# GS_02_Pow.net
KiCad netlist of a schematic drawn in Altium Designer
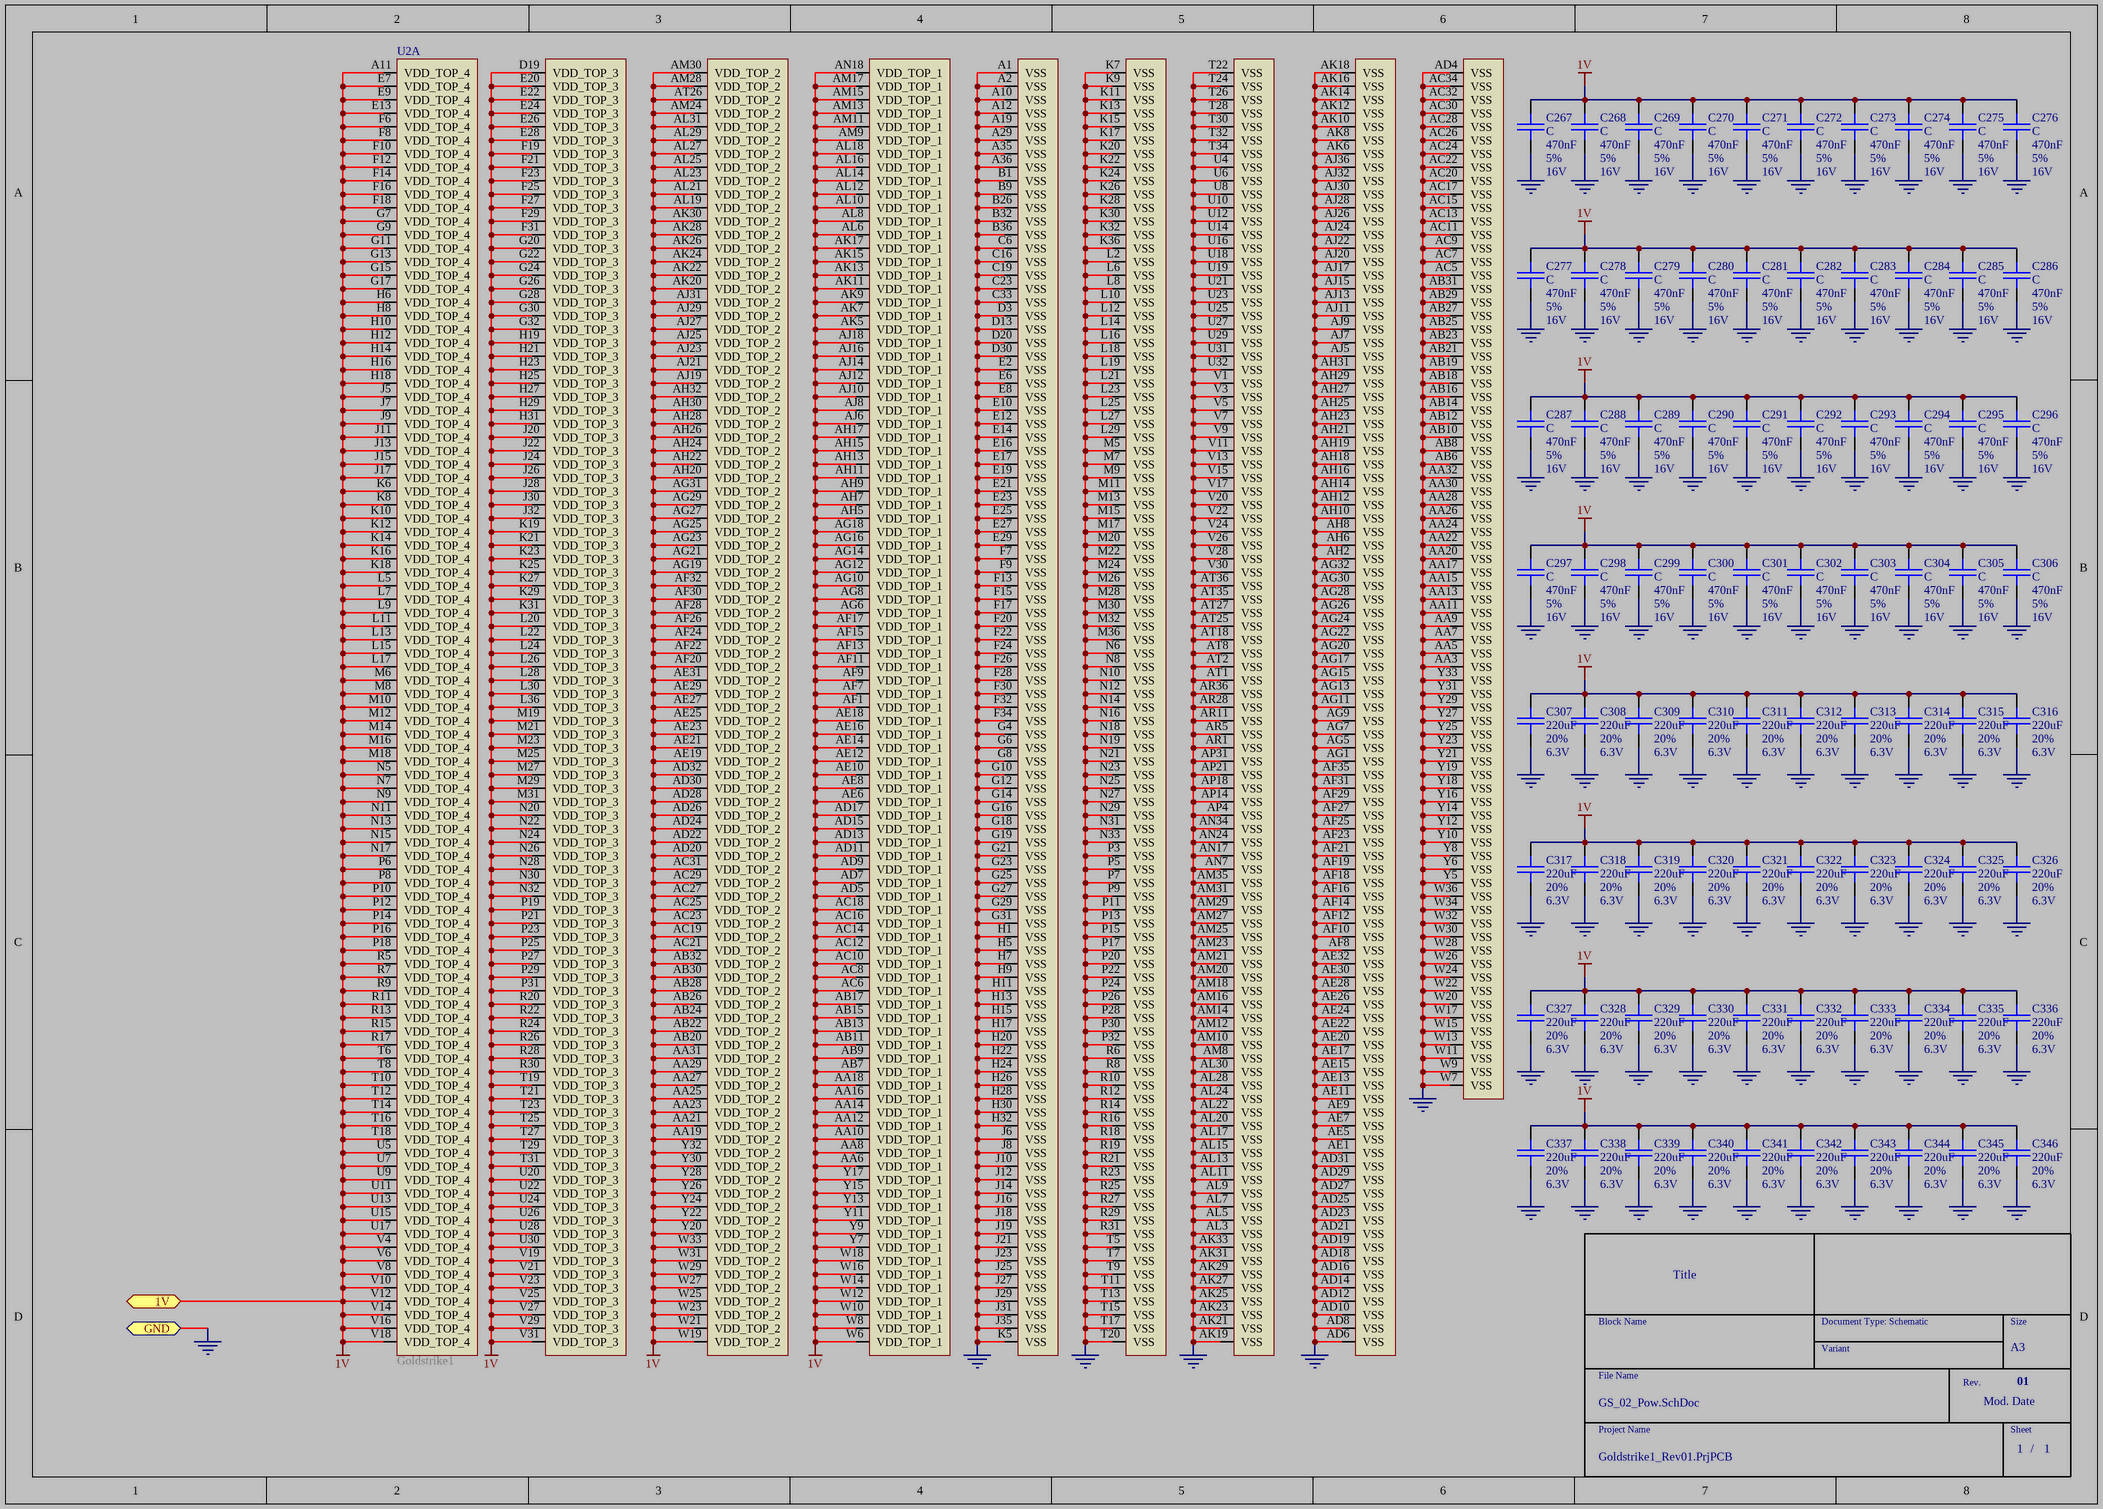
[diagram p0: GS_02_Pow.SchDoc]

(export (version "E")
  (design (tool "Eeschema 10.0.6"))
  (components
    (comp (ref "C267")
      (value "C")
      (footprint "SMD_0603_CAPC1608X95N")
      (fields
        (field (name "DB_PART_NUMBER") "CAP000028169")
        (field (name "DB_VALUE") "470nF")
        (field (name "DB_TOLERANCE") "5%")
        (field (name "DB_VOLTAGE") "16V")
        (field (name "DB_MANUFACTURER_PART") "KEMET    C0603C474J4RAC")
      )
      (libsource (lib "Database_Libs1") (part "C"))
    )
    (comp (ref "C268")
      (value "C")
      (footprint "SMD_0603_CAPC1608X95N")
      (fields
        (field (name "DB_PART_NUMBER") "CAP000028169")
        (field (name "DB_VALUE") "470nF")
        (field (name "DB_TOLERANCE") "5%")
        (field (name "DB_VOLTAGE") "16V")
        (field (name "DB_MANUFACTURER_PART") "KEMET    C0603C474J4RAC")
      )
      (libsource (lib "Database_Libs1") (part "C"))
    )
    (comp (ref "C269")
      (value "C")
      (footprint "SMD_0603_CAPC1608X95N")
      (fields
        (field (name "DB_PART_NUMBER") "CAP000028169")
        (field (name "DB_VALUE") "470nF")
        (field (name "DB_TOLERANCE") "5%")
        (field (name "DB_VOLTAGE") "16V")
        (field (name "DB_MANUFACTURER_PART") "KEMET    C0603C474J4RAC")
      )
      (libsource (lib "Database_Libs1") (part "C"))
    )
    (comp (ref "C270")
      (value "C")
      (footprint "SMD_0603_CAPC1608X95N")
      (fields
        (field (name "DB_PART_NUMBER") "CAP000028169")
        (field (name "DB_VALUE") "470nF")
        (field (name "DB_TOLERANCE") "5%")
        (field (name "DB_VOLTAGE") "16V")
        (field (name "DB_MANUFACTURER_PART") "KEMET    C0603C474J4RAC")
      )
      (libsource (lib "Database_Libs1") (part "C"))
    )
    (comp (ref "C271")
      (value "C")
      (footprint "SMD_0603_CAPC1608X95N")
      (fields
        (field (name "DB_PART_NUMBER") "CAP000028169")
        (field (name "DB_VALUE") "470nF")
        (field (name "DB_TOLERANCE") "5%")
        (field (name "DB_VOLTAGE") "16V")
        (field (name "DB_MANUFACTURER_PART") "KEMET    C0603C474J4RAC")
      )
      (libsource (lib "Database_Libs1") (part "C"))
    )
    (comp (ref "C272")
      (value "C")
      (footprint "SMD_0603_CAPC1608X95N")
      (fields
        (field (name "DB_PART_NUMBER") "CAP000028169")
        (field (name "DB_VALUE") "470nF")
        (field (name "DB_TOLERANCE") "5%")
        (field (name "DB_VOLTAGE") "16V")
        (field (name "DB_MANUFACTURER_PART") "KEMET    C0603C474J4RAC")
      )
      (libsource (lib "Database_Libs1") (part "C"))
    )
    (comp (ref "C273")
      (value "C")
      (footprint "SMD_0603_CAPC1608X95N")
      (fields
        (field (name "DB_PART_NUMBER") "CAP000028169")
        (field (name "DB_VALUE") "470nF")
        (field (name "DB_TOLERANCE") "5%")
        (field (name "DB_VOLTAGE") "16V")
        (field (name "DB_MANUFACTURER_PART") "KEMET    C0603C474J4RAC")
      )
      (libsource (lib "Database_Libs1") (part "C"))
    )
    (comp (ref "C274")
      (value "C")
      (footprint "SMD_0603_CAPC1608X95N")
      (fields
        (field (name "DB_PART_NUMBER") "CAP000028169")
        (field (name "DB_VALUE") "470nF")
        (field (name "DB_TOLERANCE") "5%")
        (field (name "DB_VOLTAGE") "16V")
        (field (name "DB_MANUFACTURER_PART") "KEMET    C0603C474J4RAC")
      )
      (libsource (lib "Database_Libs1") (part "C"))
    )
    (comp (ref "C275")
      (value "C")
      (footprint "SMD_0603_CAPC1608X95N")
      (fields
        (field (name "DB_PART_NUMBER") "CAP000028169")
        (field (name "DB_VALUE") "470nF")
        (field (name "DB_TOLERANCE") "5%")
        (field (name "DB_VOLTAGE") "16V")
        (field (name "DB_MANUFACTURER_PART") "KEMET    C0603C474J4RAC")
      )
      (libsource (lib "Database_Libs1") (part "C"))
    )
    (comp (ref "C276")
      (value "C")
      (footprint "SMD_0603_CAPC1608X95N")
      (fields
        (field (name "DB_PART_NUMBER") "CAP000028169")
        (field (name "DB_VALUE") "470nF")
        (field (name "DB_TOLERANCE") "5%")
        (field (name "DB_VOLTAGE") "16V")
        (field (name "DB_MANUFACTURER_PART") "KEMET    C0603C474J4RAC")
      )
      (libsource (lib "Database_Libs1") (part "C"))
    )
    (comp (ref "C277")
      (value "C")
      (footprint "SMD_0603_CAPC1608X95N")
      (fields
        (field (name "DB_PART_NUMBER") "CAP000028169")
        (field (name "DB_VALUE") "470nF")
        (field (name "DB_TOLERANCE") "5%")
        (field (name "DB_VOLTAGE") "16V")
        (field (name "DB_MANUFACTURER_PART") "KEMET    C0603C474J4RAC")
      )
      (libsource (lib "Database_Libs1") (part "C"))
    )
    (comp (ref "C278")
      (value "C")
      (footprint "SMD_0603_CAPC1608X95N")
      (fields
        (field (name "DB_PART_NUMBER") "CAP000028169")
        (field (name "DB_VALUE") "470nF")
        (field (name "DB_TOLERANCE") "5%")
        (field (name "DB_VOLTAGE") "16V")
        (field (name "DB_MANUFACTURER_PART") "KEMET    C0603C474J4RAC")
      )
      (libsource (lib "Database_Libs1") (part "C"))
    )
    (comp (ref "C279")
      (value "C")
      (footprint "SMD_0603_CAPC1608X95N")
      (fields
        (field (name "DB_PART_NUMBER") "CAP000028169")
        (field (name "DB_VALUE") "470nF")
        (field (name "DB_TOLERANCE") "5%")
        (field (name "DB_VOLTAGE") "16V")
        (field (name "DB_MANUFACTURER_PART") "KEMET    C0603C474J4RAC")
      )
      (libsource (lib "Database_Libs1") (part "C"))
    )
    (comp (ref "C280")
      (value "C")
      (footprint "SMD_0603_CAPC1608X95N")
      (fields
        (field (name "DB_PART_NUMBER") "CAP000028169")
        (field (name "DB_VALUE") "470nF")
        (field (name "DB_TOLERANCE") "5%")
        (field (name "DB_VOLTAGE") "16V")
        (field (name "DB_MANUFACTURER_PART") "KEMET    C0603C474J4RAC")
      )
      (libsource (lib "Database_Libs1") (part "C"))
    )
    (comp (ref "C281")
      (value "C")
      (footprint "SMD_0603_CAPC1608X95N")
      (fields
        (field (name "DB_PART_NUMBER") "CAP000028169")
        (field (name "DB_VALUE") "470nF")
        (field (name "DB_TOLERANCE") "5%")
        (field (name "DB_VOLTAGE") "16V")
        (field (name "DB_MANUFACTURER_PART") "KEMET    C0603C474J4RAC")
      )
      (libsource (lib "Database_Libs1") (part "C"))
    )
    (comp (ref "C282")
      (value "C")
      (footprint "SMD_0603_CAPC1608X95N")
      (fields
        (field (name "DB_PART_NUMBER") "CAP000028169")
        (field (name "DB_VALUE") "470nF")
        (field (name "DB_TOLERANCE") "5%")
        (field (name "DB_VOLTAGE") "16V")
        (field (name "DB_MANUFACTURER_PART") "KEMET    C0603C474J4RAC")
      )
      (libsource (lib "Database_Libs1") (part "C"))
    )
    (comp (ref "C283")
      (value "C")
      (footprint "SMD_0603_CAPC1608X95N")
      (fields
        (field (name "DB_PART_NUMBER") "CAP000028169")
        (field (name "DB_VALUE") "470nF")
        (field (name "DB_TOLERANCE") "5%")
        (field (name "DB_VOLTAGE") "16V")
        (field (name "DB_MANUFACTURER_PART") "KEMET    C0603C474J4RAC")
      )
      (libsource (lib "Database_Libs1") (part "C"))
    )
    (comp (ref "C284")
      (value "C")
      (footprint "SMD_0603_CAPC1608X95N")
      (fields
        (field (name "DB_PART_NUMBER") "CAP000028169")
        (field (name "DB_VALUE") "470nF")
        (field (name "DB_TOLERANCE") "5%")
        (field (name "DB_VOLTAGE") "16V")
        (field (name "DB_MANUFACTURER_PART") "KEMET    C0603C474J4RAC")
      )
      (libsource (lib "Database_Libs1") (part "C"))
    )
    (comp (ref "C285")
      (value "C")
      (footprint "SMD_0603_CAPC1608X95N")
      (fields
        (field (name "DB_PART_NUMBER") "CAP000028169")
        (field (name "DB_VALUE") "470nF")
        (field (name "DB_TOLERANCE") "5%")
        (field (name "DB_VOLTAGE") "16V")
        (field (name "DB_MANUFACTURER_PART") "KEMET    C0603C474J4RAC")
      )
      (libsource (lib "Database_Libs1") (part "C"))
    )
    (comp (ref "C286")
      (value "C")
      (footprint "SMD_0603_CAPC1608X95N")
      (fields
        (field (name "DB_PART_NUMBER") "CAP000028169")
        (field (name "DB_VALUE") "470nF")
        (field (name "DB_TOLERANCE") "5%")
        (field (name "DB_VOLTAGE") "16V")
        (field (name "DB_MANUFACTURER_PART") "KEMET    C0603C474J4RAC")
      )
      (libsource (lib "Database_Libs1") (part "C"))
    )
    (comp (ref "C287")
      (value "C")
      (footprint "SMD_0603_CAPC1608X95N")
      (fields
        (field (name "DB_PART_NUMBER") "CAP000028169")
        (field (name "DB_VALUE") "470nF")
        (field (name "DB_TOLERANCE") "5%")
        (field (name "DB_VOLTAGE") "16V")
        (field (name "DB_MANUFACTURER_PART") "KEMET    C0603C474J4RAC")
      )
      (libsource (lib "Database_Libs1") (part "C"))
    )
    (comp (ref "C288")
      (value "C")
      (footprint "SMD_0603_CAPC1608X95N")
      (fields
        (field (name "DB_PART_NUMBER") "CAP000028169")
        (field (name "DB_VALUE") "470nF")
        (field (name "DB_TOLERANCE") "5%")
        (field (name "DB_VOLTAGE") "16V")
        (field (name "DB_MANUFACTURER_PART") "KEMET    C0603C474J4RAC")
      )
      (libsource (lib "Database_Libs1") (part "C"))
    )
    (comp (ref "C289")
      (value "C")
      (footprint "SMD_0603_CAPC1608X95N")
      (fields
        (field (name "DB_PART_NUMBER") "CAP000028169")
        (field (name "DB_VALUE") "470nF")
        (field (name "DB_TOLERANCE") "5%")
        (field (name "DB_VOLTAGE") "16V")
        (field (name "DB_MANUFACTURER_PART") "KEMET    C0603C474J4RAC")
      )
      (libsource (lib "Database_Libs1") (part "C"))
    )
    (comp (ref "C290")
      (value "C")
      (footprint "SMD_0603_CAPC1608X95N")
      (fields
        (field (name "DB_PART_NUMBER") "CAP000028169")
        (field (name "DB_VALUE") "470nF")
        (field (name "DB_TOLERANCE") "5%")
        (field (name "DB_VOLTAGE") "16V")
        (field (name "DB_MANUFACTURER_PART") "KEMET    C0603C474J4RAC")
      )
      (libsource (lib "Database_Libs1") (part "C"))
    )
    (comp (ref "C291")
      (value "C")
      (footprint "SMD_0603_CAPC1608X95N")
      (fields
        (field (name "DB_PART_NUMBER") "CAP000028169")
        (field (name "DB_VALUE") "470nF")
        (field (name "DB_TOLERANCE") "5%")
        (field (name "DB_VOLTAGE") "16V")
        (field (name "DB_MANUFACTURER_PART") "KEMET    C0603C474J4RAC")
      )
      (libsource (lib "Database_Libs1") (part "C"))
    )
    (comp (ref "C292")
      (value "C")
      (footprint "SMD_0603_CAPC1608X95N")
      (fields
        (field (name "DB_PART_NUMBER") "CAP000028169")
        (field (name "DB_VALUE") "470nF")
        (field (name "DB_TOLERANCE") "5%")
        (field (name "DB_VOLTAGE") "16V")
        (field (name "DB_MANUFACTURER_PART") "KEMET    C0603C474J4RAC")
      )
      (libsource (lib "Database_Libs1") (part "C"))
    )
    (comp (ref "C293")
      (value "C")
      (footprint "SMD_0603_CAPC1608X95N")
      (fields
        (field (name "DB_PART_NUMBER") "CAP000028169")
        (field (name "DB_VALUE") "470nF")
        (field (name "DB_TOLERANCE") "5%")
        (field (name "DB_VOLTAGE") "16V")
        (field (name "DB_MANUFACTURER_PART") "KEMET    C0603C474J4RAC")
      )
      (libsource (lib "Database_Libs1") (part "C"))
    )
    (comp (ref "C294")
      (value "C")
      (footprint "SMD_0603_CAPC1608X95N")
      (fields
        (field (name "DB_PART_NUMBER") "CAP000028169")
        (field (name "DB_VALUE") "470nF")
        (field (name "DB_TOLERANCE") "5%")
        (field (name "DB_VOLTAGE") "16V")
        (field (name "DB_MANUFACTURER_PART") "KEMET    C0603C474J4RAC")
      )
      (libsource (lib "Database_Libs1") (part "C"))
    )
    (comp (ref "C295")
      (value "C")
      (footprint "SMD_0603_CAPC1608X95N")
      (fields
        (field (name "DB_PART_NUMBER") "CAP000028169")
        (field (name "DB_VALUE") "470nF")
        (field (name "DB_TOLERANCE") "5%")
        (field (name "DB_VOLTAGE") "16V")
        (field (name "DB_MANUFACTURER_PART") "KEMET    C0603C474J4RAC")
      )
      (libsource (lib "Database_Libs1") (part "C"))
    )
    (comp (ref "C296")
      (value "C")
      (footprint "SMD_0603_CAPC1608X95N")
      (fields
        (field (name "DB_PART_NUMBER") "CAP000028169")
        (field (name "DB_VALUE") "470nF")
        (field (name "DB_TOLERANCE") "5%")
        (field (name "DB_VOLTAGE") "16V")
        (field (name "DB_MANUFACTURER_PART") "KEMET    C0603C474J4RAC")
      )
      (libsource (lib "Database_Libs1") (part "C"))
    )
    (comp (ref "C297")
      (value "C")
      (footprint "SMD_0603_CAPC1608X95N")
      (fields
        (field (name "DB_PART_NUMBER") "CAP000028169")
        (field (name "DB_VALUE") "470nF")
        (field (name "DB_TOLERANCE") "5%")
        (field (name "DB_VOLTAGE") "16V")
        (field (name "DB_MANUFACTURER_PART") "KEMET    C0603C474J4RAC")
      )
      (libsource (lib "Database_Libs1") (part "C"))
    )
    (comp (ref "C298")
      (value "C")
      (footprint "SMD_0603_CAPC1608X95N")
      (fields
        (field (name "DB_PART_NUMBER") "CAP000028169")
        (field (name "DB_VALUE") "470nF")
        (field (name "DB_TOLERANCE") "5%")
        (field (name "DB_VOLTAGE") "16V")
        (field (name "DB_MANUFACTURER_PART") "KEMET    C0603C474J4RAC")
      )
      (libsource (lib "Database_Libs1") (part "C"))
    )
    (comp (ref "C299")
      (value "C")
      (footprint "SMD_0603_CAPC1608X95N")
      (fields
        (field (name "DB_PART_NUMBER") "CAP000028169")
        (field (name "DB_VALUE") "470nF")
        (field (name "DB_TOLERANCE") "5%")
        (field (name "DB_VOLTAGE") "16V")
        (field (name "DB_MANUFACTURER_PART") "KEMET    C0603C474J4RAC")
      )
      (libsource (lib "Database_Libs1") (part "C"))
    )
    (comp (ref "C300")
      (value "C")
      (footprint "SMD_0603_CAPC1608X95N")
      (fields
        (field (name "DB_PART_NUMBER") "CAP000028169")
        (field (name "DB_VALUE") "470nF")
        (field (name "DB_TOLERANCE") "5%")
        (field (name "DB_VOLTAGE") "16V")
        (field (name "DB_MANUFACTURER_PART") "KEMET    C0603C474J4RAC")
      )
      (libsource (lib "Database_Libs1") (part "C"))
    )
    (comp (ref "C301")
      (value "C")
      (footprint "SMD_0603_CAPC1608X95N")
      (fields
        (field (name "DB_PART_NUMBER") "CAP000028169")
        (field (name "DB_VALUE") "470nF")
        (field (name "DB_TOLERANCE") "5%")
        (field (name "DB_VOLTAGE") "16V")
        (field (name "DB_MANUFACTURER_PART") "KEMET    C0603C474J4RAC")
      )
      (libsource (lib "Database_Libs1") (part "C"))
    )
    (comp (ref "C302")
      (value "C")
      (footprint "SMD_0603_CAPC1608X95N")
      (fields
        (field (name "DB_PART_NUMBER") "CAP000028169")
        (field (name "DB_VALUE") "470nF")
        (field (name "DB_TOLERANCE") "5%")
        (field (name "DB_VOLTAGE") "16V")
        (field (name "DB_MANUFACTURER_PART") "KEMET    C0603C474J4RAC")
      )
      (libsource (lib "Database_Libs1") (part "C"))
    )
    (comp (ref "C303")
      (value "C")
      (footprint "SMD_0603_CAPC1608X95N")
      (fields
        (field (name "DB_PART_NUMBER") "CAP000028169")
        (field (name "DB_VALUE") "470nF")
        (field (name "DB_TOLERANCE") "5%")
        (field (name "DB_VOLTAGE") "16V")
        (field (name "DB_MANUFACTURER_PART") "KEMET    C0603C474J4RAC")
      )
      (libsource (lib "Database_Libs1") (part "C"))
    )
    (comp (ref "C304")
      (value "C")
      (footprint "SMD_0603_CAPC1608X95N")
      (fields
        (field (name "DB_PART_NUMBER") "CAP000028169")
        (field (name "DB_VALUE") "470nF")
        (field (name "DB_TOLERANCE") "5%")
        (field (name "DB_VOLTAGE") "16V")
        (field (name "DB_MANUFACTURER_PART") "KEMET    C0603C474J4RAC")
      )
      (libsource (lib "Database_Libs1") (part "C"))
    )
    (comp (ref "C305")
      (value "C")
      (footprint "SMD_0603_CAPC1608X95N")
      (fields
        (field (name "DB_PART_NUMBER") "CAP000028169")
        (field (name "DB_VALUE") "470nF")
        (field (name "DB_TOLERANCE") "5%")
        (field (name "DB_VOLTAGE") "16V")
        (field (name "DB_MANUFACTURER_PART") "KEMET    C0603C474J4RAC")
      )
      (libsource (lib "Database_Libs1") (part "C"))
    )
    (comp (ref "C306")
      (value "C")
      (footprint "SMD_0603_CAPC1608X95N")
      (fields
        (field (name "DB_PART_NUMBER") "CAP000028169")
        (field (name "DB_VALUE") "470nF")
        (field (name "DB_TOLERANCE") "5%")
        (field (name "DB_VOLTAGE") "16V")
        (field (name "DB_MANUFACTURER_PART") "KEMET    C0603C474J4RAC")
      )
      (libsource (lib "Database_Libs1") (part "C"))
    )
    (comp (ref "C307")
      (value "C")
      (footprint "SMD_1210_CAPC3225X279N")
      (fields
        (field (name "DB_PART_NUMBER") "CAP000047355")
        (field (name "DB_VALUE") "220uF")
        (field (name "DB_TOLERANCE") "20%")
        (field (name "DB_VOLTAGE") "6.3V")
        (field (name "DB_MANUFACTURER_PART") "SAMSUNG    CL32A227MQVNNNE")
        (field (name "DB_APPROVED_BY") "VSN")
      )
      (libsource (lib "Database_Libs1") (part "C"))
    )
    (comp (ref "C308")
      (value "C")
      (footprint "SMD_1210_CAPC3225X279N")
      (fields
        (field (name "DB_PART_NUMBER") "CAP000047355")
        (field (name "DB_VALUE") "220uF")
        (field (name "DB_TOLERANCE") "20%")
        (field (name "DB_VOLTAGE") "6.3V")
        (field (name "DB_MANUFACTURER_PART") "SAMSUNG    CL32A227MQVNNNE")
        (field (name "DB_APPROVED_BY") "VSN")
      )
      (libsource (lib "Database_Libs1") (part "C"))
    )
    (comp (ref "C309")
      (value "C")
      (footprint "SMD_1210_CAPC3225X279N")
      (fields
        (field (name "DB_PART_NUMBER") "CAP000047355")
        (field (name "DB_VALUE") "220uF")
        (field (name "DB_TOLERANCE") "20%")
        (field (name "DB_VOLTAGE") "6.3V")
        (field (name "DB_MANUFACTURER_PART") "SAMSUNG    CL32A227MQVNNNE")
        (field (name "DB_APPROVED_BY") "VSN")
      )
      (libsource (lib "Database_Libs1") (part "C"))
    )
    (comp (ref "C310")
      (value "C")
      (footprint "SMD_1210_CAPC3225X279N")
      (fields
        (field (name "DB_PART_NUMBER") "CAP000047355")
        (field (name "DB_VALUE") "220uF")
        (field (name "DB_TOLERANCE") "20%")
        (field (name "DB_VOLTAGE") "6.3V")
        (field (name "DB_MANUFACTURER_PART") "SAMSUNG    CL32A227MQVNNNE")
        (field (name "DB_APPROVED_BY") "VSN")
      )
      (libsource (lib "Database_Libs1") (part "C"))
    )
    (comp (ref "C311")
      (value "C")
      (footprint "SMD_1210_CAPC3225X279N")
      (fields
        (field (name "DB_PART_NUMBER") "CAP000047355")
        (field (name "DB_VALUE") "220uF")
        (field (name "DB_TOLERANCE") "20%")
        (field (name "DB_VOLTAGE") "6.3V")
        (field (name "DB_MANUFACTURER_PART") "SAMSUNG    CL32A227MQVNNNE")
        (field (name "DB_APPROVED_BY") "VSN")
      )
      (libsource (lib "Database_Libs1") (part "C"))
    )
    (comp (ref "C312")
      (value "C")
      (footprint "SMD_1210_CAPC3225X279N")
      (fields
        (field (name "DB_PART_NUMBER") "CAP000047355")
        (field (name "DB_VALUE") "220uF")
        (field (name "DB_TOLERANCE") "20%")
        (field (name "DB_VOLTAGE") "6.3V")
        (field (name "DB_MANUFACTURER_PART") "SAMSUNG    CL32A227MQVNNNE")
        (field (name "DB_APPROVED_BY") "VSN")
      )
      (libsource (lib "Database_Libs1") (part "C"))
    )
    (comp (ref "C313")
      (value "C")
      (footprint "SMD_1210_CAPC3225X279N")
      (fields
        (field (name "DB_PART_NUMBER") "CAP000047355")
        (field (name "DB_VALUE") "220uF")
        (field (name "DB_TOLERANCE") "20%")
        (field (name "DB_VOLTAGE") "6.3V")
        (field (name "DB_MANUFACTURER_PART") "SAMSUNG    CL32A227MQVNNNE")
        (field (name "DB_APPROVED_BY") "VSN")
      )
      (libsource (lib "Database_Libs1") (part "C"))
    )
    (comp (ref "C314")
      (value "C")
      (footprint "SMD_1210_CAPC3225X279N")
      (fields
        (field (name "DB_PART_NUMBER") "CAP000047355")
        (field (name "DB_VALUE") "220uF")
        (field (name "DB_TOLERANCE") "20%")
        (field (name "DB_VOLTAGE") "6.3V")
        (field (name "DB_MANUFACTURER_PART") "SAMSUNG    CL32A227MQVNNNE")
        (field (name "DB_APPROVED_BY") "VSN")
      )
      (libsource (lib "Database_Libs1") (part "C"))
    )
    (comp (ref "C315")
      (value "C")
      (footprint "SMD_1210_CAPC3225X279N")
      (fields
        (field (name "DB_PART_NUMBER") "CAP000047355")
        (field (name "DB_VALUE") "220uF")
        (field (name "DB_TOLERANCE") "20%")
        (field (name "DB_VOLTAGE") "6.3V")
        (field (name "DB_MANUFACTURER_PART") "SAMSUNG    CL32A227MQVNNNE")
        (field (name "DB_APPROVED_BY") "VSN")
      )
      (libsource (lib "Database_Libs1") (part "C"))
    )
    (comp (ref "C316")
      (value "C")
      (footprint "SMD_1210_CAPC3225X279N")
      (fields
        (field (name "DB_PART_NUMBER") "CAP000047355")
        (field (name "DB_VALUE") "220uF")
        (field (name "DB_TOLERANCE") "20%")
        (field (name "DB_VOLTAGE") "6.3V")
        (field (name "DB_MANUFACTURER_PART") "SAMSUNG    CL32A227MQVNNNE")
        (field (name "DB_APPROVED_BY") "VSN")
      )
      (libsource (lib "Database_Libs1") (part "C"))
    )
    (comp (ref "C317")
      (value "C")
      (footprint "SMD_1210_CAPC3225X279N")
      (fields
        (field (name "DB_PART_NUMBER") "CAP000047355")
        (field (name "DB_VALUE") "220uF")
        (field (name "DB_TOLERANCE") "20%")
        (field (name "DB_VOLTAGE") "6.3V")
        (field (name "DB_MANUFACTURER_PART") "SAMSUNG    CL32A227MQVNNNE")
        (field (name "DB_APPROVED_BY") "VSN")
      )
      (libsource (lib "Database_Libs1") (part "C"))
    )
    (comp (ref "C318")
      (value "C")
      (footprint "SMD_1210_CAPC3225X279N")
      (fields
        (field (name "DB_PART_NUMBER") "CAP000047355")
        (field (name "DB_VALUE") "220uF")
        (field (name "DB_TOLERANCE") "20%")
        (field (name "DB_VOLTAGE") "6.3V")
        (field (name "DB_MANUFACTURER_PART") "SAMSUNG    CL32A227MQVNNNE")
        (field (name "DB_APPROVED_BY") "VSN")
      )
      (libsource (lib "Database_Libs1") (part "C"))
    )
    (comp (ref "C319")
      (value "C")
      (footprint "SMD_1210_CAPC3225X279N")
      (fields
        (field (name "DB_PART_NUMBER") "CAP000047355")
        (field (name "DB_VALUE") "220uF")
        (field (name "DB_TOLERANCE") "20%")
        (field (name "DB_VOLTAGE") "6.3V")
        (field (name "DB_MANUFACTURER_PART") "SAMSUNG    CL32A227MQVNNNE")
        (field (name "DB_APPROVED_BY") "VSN")
      )
      (libsource (lib "Database_Libs1") (part "C"))
    )
    (comp (ref "C320")
      (value "C")
      (footprint "SMD_1210_CAPC3225X279N")
      (fields
        (field (name "DB_PART_NUMBER") "CAP000047355")
        (field (name "DB_VALUE") "220uF")
        (field (name "DB_TOLERANCE") "20%")
        (field (name "DB_VOLTAGE") "6.3V")
        (field (name "DB_MANUFACTURER_PART") "SAMSUNG    CL32A227MQVNNNE")
        (field (name "DB_APPROVED_BY") "VSN")
      )
      (libsource (lib "Database_Libs1") (part "C"))
    )
    (comp (ref "C321")
      (value "C")
      (footprint "SMD_1210_CAPC3225X279N")
      (fields
        (field (name "DB_PART_NUMBER") "CAP000047355")
        (field (name "DB_VALUE") "220uF")
        (field (name "DB_TOLERANCE") "20%")
        (field (name "DB_VOLTAGE") "6.3V")
        (field (name "DB_MANUFACTURER_PART") "SAMSUNG    CL32A227MQVNNNE")
        (field (name "DB_APPROVED_BY") "VSN")
      )
      (libsource (lib "Database_Libs1") (part "C"))
    )
    (comp (ref "C322")
      (value "C")
      (footprint "SMD_1210_CAPC3225X279N")
      (fields
        (field (name "DB_PART_NUMBER") "CAP000047355")
        (field (name "DB_VALUE") "220uF")
        (field (name "DB_TOLERANCE") "20%")
        (field (name "DB_VOLTAGE") "6.3V")
        (field (name "DB_MANUFACTURER_PART") "SAMSUNG    CL32A227MQVNNNE")
        (field (name "DB_APPROVED_BY") "VSN")
      )
      (libsource (lib "Database_Libs1") (part "C"))
    )
    (comp (ref "C323")
      (value "C")
      (footprint "SMD_1210_CAPC3225X279N")
      (fields
        (field (name "DB_PART_NUMBER") "CAP000047355")
        (field (name "DB_VALUE") "220uF")
        (field (name "DB_TOLERANCE") "20%")
        (field (name "DB_VOLTAGE") "6.3V")
        (field (name "DB_MANUFACTURER_PART") "SAMSUNG    CL32A227MQVNNNE")
        (field (name "DB_APPROVED_BY") "VSN")
      )
      (libsource (lib "Database_Libs1") (part "C"))
    )
    (comp (ref "C324")
      (value "C")
      (footprint "SMD_1210_CAPC3225X279N")
      (fields
        (field (name "DB_PART_NUMBER") "CAP000047355")
        (field (name "DB_VALUE") "220uF")
        (field (name "DB_TOLERANCE") "20%")
        (field (name "DB_VOLTAGE") "6.3V")
        (field (name "DB_MANUFACTURER_PART") "SAMSUNG    CL32A227MQVNNNE")
        (field (name "DB_APPROVED_BY") "VSN")
      )
      (libsource (lib "Database_Libs1") (part "C"))
    )
    (comp (ref "C325")
      (value "C")
      (footprint "SMD_1210_CAPC3225X279N")
      (fields
        (field (name "DB_PART_NUMBER") "CAP000047355")
        (field (name "DB_VALUE") "220uF")
        (field (name "DB_TOLERANCE") "20%")
        (field (name "DB_VOLTAGE") "6.3V")
        (field (name "DB_MANUFACTURER_PART") "SAMSUNG    CL32A227MQVNNNE")
        (field (name "DB_APPROVED_BY") "VSN")
      )
      (libsource (lib "Database_Libs1") (part "C"))
    )
    (comp (ref "C326")
      (value "C")
      (footprint "SMD_1210_CAPC3225X279N")
      (fields
        (field (name "DB_PART_NUMBER") "CAP000047355")
        (field (name "DB_VALUE") "220uF")
        (field (name "DB_TOLERANCE") "20%")
        (field (name "DB_VOLTAGE") "6.3V")
        (field (name "DB_MANUFACTURER_PART") "SAMSUNG    CL32A227MQVNNNE")
        (field (name "DB_APPROVED_BY") "VSN")
      )
      (libsource (lib "Database_Libs1") (part "C"))
    )
    (comp (ref "C327")
      (value "C")
      (footprint "SMD_1210_CAPC3225X279N")
      (fields
        (field (name "DB_PART_NUMBER") "CAP000047355")
        (field (name "DB_VALUE") "220uF")
        (field (name "DB_TOLERANCE") "20%")
        (field (name "DB_VOLTAGE") "6.3V")
        (field (name "DB_MANUFACTURER_PART") "SAMSUNG    CL32A227MQVNNNE")
        (field (name "DB_APPROVED_BY") "VSN")
      )
      (libsource (lib "Database_Libs1") (part "C"))
    )
    (comp (ref "C328")
      (value "C")
      (footprint "SMD_1210_CAPC3225X279N")
      (fields
        (field (name "DB_PART_NUMBER") "CAP000047355")
        (field (name "DB_VALUE") "220uF")
        (field (name "DB_TOLERANCE") "20%")
        (field (name "DB_VOLTAGE") "6.3V")
        (field (name "DB_MANUFACTURER_PART") "SAMSUNG    CL32A227MQVNNNE")
        (field (name "DB_APPROVED_BY") "VSN")
      )
      (libsource (lib "Database_Libs1") (part "C"))
    )
    (comp (ref "C329")
      (value "C")
      (footprint "SMD_1210_CAPC3225X279N")
      (fields
        (field (name "DB_PART_NUMBER") "CAP000047355")
        (field (name "DB_VALUE") "220uF")
        (field (name "DB_TOLERANCE") "20%")
        (field (name "DB_VOLTAGE") "6.3V")
        (field (name "DB_MANUFACTURER_PART") "SAMSUNG    CL32A227MQVNNNE")
        (field (name "DB_APPROVED_BY") "VSN")
      )
      (libsource (lib "Database_Libs1") (part "C"))
    )
    (comp (ref "C330")
      (value "C")
      (footprint "SMD_1210_CAPC3225X279N")
      (fields
        (field (name "DB_PART_NUMBER") "CAP000047355")
        (field (name "DB_VALUE") "220uF")
        (field (name "DB_TOLERANCE") "20%")
        (field (name "DB_VOLTAGE") "6.3V")
        (field (name "DB_MANUFACTURER_PART") "SAMSUNG    CL32A227MQVNNNE")
        (field (name "DB_APPROVED_BY") "VSN")
      )
      (libsource (lib "Database_Libs1") (part "C"))
    )
    (comp (ref "C331")
      (value "C")
      (footprint "SMD_1210_CAPC3225X279N")
      (fields
        (field (name "DB_PART_NUMBER") "CAP000047355")
        (field (name "DB_VALUE") "220uF")
        (field (name "DB_TOLERANCE") "20%")
        (field (name "DB_VOLTAGE") "6.3V")
        (field (name "DB_MANUFACTURER_PART") "SAMSUNG    CL32A227MQVNNNE")
        (field (name "DB_APPROVED_BY") "VSN")
      )
      (libsource (lib "Database_Libs1") (part "C"))
    )
    (comp (ref "C332")
      (value "C")
      (footprint "SMD_1210_CAPC3225X279N")
      (fields
        (field (name "DB_PART_NUMBER") "CAP000047355")
        (field (name "DB_VALUE") "220uF")
        (field (name "DB_TOLERANCE") "20%")
        (field (name "DB_VOLTAGE") "6.3V")
        (field (name "DB_MANUFACTURER_PART") "SAMSUNG    CL32A227MQVNNNE")
        (field (name "DB_APPROVED_BY") "VSN")
      )
      (libsource (lib "Database_Libs1") (part "C"))
    )
    (comp (ref "C333")
      (value "C")
      (footprint "SMD_1210_CAPC3225X279N")
      (fields
        (field (name "DB_PART_NUMBER") "CAP000047355")
        (field (name "DB_VALUE") "220uF")
        (field (name "DB_TOLERANCE") "20%")
        (field (name "DB_VOLTAGE") "6.3V")
        (field (name "DB_MANUFACTURER_PART") "SAMSUNG    CL32A227MQVNNNE")
        (field (name "DB_APPROVED_BY") "VSN")
      )
      (libsource (lib "Database_Libs1") (part "C"))
    )
    (comp (ref "C334")
      (value "C")
      (footprint "SMD_1210_CAPC3225X279N")
      (fields
        (field (name "DB_PART_NUMBER") "CAP000047355")
        (field (name "DB_VALUE") "220uF")
        (field (name "DB_TOLERANCE") "20%")
        (field (name "DB_VOLTAGE") "6.3V")
        (field (name "DB_MANUFACTURER_PART") "SAMSUNG    CL32A227MQVNNNE")
        (field (name "DB_APPROVED_BY") "VSN")
      )
      (libsource (lib "Database_Libs1") (part "C"))
    )
    (comp (ref "C335")
      (value "C")
      (footprint "SMD_1210_CAPC3225X279N")
      (fields
        (field (name "DB_PART_NUMBER") "CAP000047355")
        (field (name "DB_VALUE") "220uF")
        (field (name "DB_TOLERANCE") "20%")
        (field (name "DB_VOLTAGE") "6.3V")
        (field (name "DB_MANUFACTURER_PART") "SAMSUNG    CL32A227MQVNNNE")
        (field (name "DB_APPROVED_BY") "VSN")
      )
      (libsource (lib "Database_Libs1") (part "C"))
    )
    (comp (ref "C336")
      (value "C")
      (footprint "SMD_1210_CAPC3225X279N")
      (fields
        (field (name "DB_PART_NUMBER") "CAP000047355")
        (field (name "DB_VALUE") "220uF")
        (field (name "DB_TOLERANCE") "20%")
        (field (name "DB_VOLTAGE") "6.3V")
        (field (name "DB_MANUFACTURER_PART") "SAMSUNG    CL32A227MQVNNNE")
        (field (name "DB_APPROVED_BY") "VSN")
      )
      (libsource (lib "Database_Libs1") (part "C"))
    )
    (comp (ref "C337")
      (value "C")
      (footprint "SMD_1210_CAPC3225X279N")
      (fields
        (field (name "DB_PART_NUMBER") "CAP000047355")
        (field (name "DB_VALUE") "220uF")
        (field (name "DB_TOLERANCE") "20%")
        (field (name "DB_VOLTAGE") "6.3V")
        (field (name "DB_MANUFACTURER_PART") "SAMSUNG    CL32A227MQVNNNE")
        (field (name "DB_APPROVED_BY") "VSN")
      )
      (libsource (lib "Database_Libs1") (part "C"))
    )
    (comp (ref "C338")
      (value "C")
      (footprint "SMD_1210_CAPC3225X279N")
      (fields
        (field (name "DB_PART_NUMBER") "CAP000047355")
        (field (name "DB_VALUE") "220uF")
        (field (name "DB_TOLERANCE") "20%")
        (field (name "DB_VOLTAGE") "6.3V")
        (field (name "DB_MANUFACTURER_PART") "SAMSUNG    CL32A227MQVNNNE")
        (field (name "DB_APPROVED_BY") "VSN")
      )
      (libsource (lib "Database_Libs1") (part "C"))
    )
    (comp (ref "C339")
      (value "C")
      (footprint "SMD_1210_CAPC3225X279N")
      (fields
        (field (name "DB_PART_NUMBER") "CAP000047355")
        (field (name "DB_VALUE") "220uF")
        (field (name "DB_TOLERANCE") "20%")
        (field (name "DB_VOLTAGE") "6.3V")
        (field (name "DB_MANUFACTURER_PART") "SAMSUNG    CL32A227MQVNNNE")
        (field (name "DB_APPROVED_BY") "VSN")
      )
      (libsource (lib "Database_Libs1") (part "C"))
    )
    (comp (ref "C340")
      (value "C")
      (footprint "SMD_1210_CAPC3225X279N")
      (fields
        (field (name "DB_PART_NUMBER") "CAP000047355")
        (field (name "DB_VALUE") "220uF")
        (field (name "DB_TOLERANCE") "20%")
        (field (name "DB_VOLTAGE") "6.3V")
        (field (name "DB_MANUFACTURER_PART") "SAMSUNG    CL32A227MQVNNNE")
        (field (name "DB_APPROVED_BY") "VSN")
      )
      (libsource (lib "Database_Libs1") (part "C"))
    )
    (comp (ref "C341")
      (value "C")
      (footprint "SMD_1210_CAPC3225X279N")
      (fields
        (field (name "DB_PART_NUMBER") "CAP000047355")
        (field (name "DB_VALUE") "220uF")
        (field (name "DB_TOLERANCE") "20%")
        (field (name "DB_VOLTAGE") "6.3V")
        (field (name "DB_MANUFACTURER_PART") "SAMSUNG    CL32A227MQVNNNE")
        (field (name "DB_APPROVED_BY") "VSN")
      )
      (libsource (lib "Database_Libs1") (part "C"))
    )
    (comp (ref "C342")
      (value "C")
      (footprint "SMD_1210_CAPC3225X279N")
      (fields
        (field (name "DB_PART_NUMBER") "CAP000047355")
        (field (name "DB_VALUE") "220uF")
        (field (name "DB_TOLERANCE") "20%")
        (field (name "DB_VOLTAGE") "6.3V")
        (field (name "DB_MANUFACTURER_PART") "SAMSUNG    CL32A227MQVNNNE")
        (field (name "DB_APPROVED_BY") "VSN")
      )
      (libsource (lib "Database_Libs1") (part "C"))
    )
    (comp (ref "C343")
      (value "C")
      (footprint "SMD_1210_CAPC3225X279N")
      (fields
        (field (name "DB_PART_NUMBER") "CAP000047355")
        (field (name "DB_VALUE") "220uF")
        (field (name "DB_TOLERANCE") "20%")
        (field (name "DB_VOLTAGE") "6.3V")
        (field (name "DB_MANUFACTURER_PART") "SAMSUNG    CL32A227MQVNNNE")
        (field (name "DB_APPROVED_BY") "VSN")
      )
      (libsource (lib "Database_Libs1") (part "C"))
    )
    (comp (ref "C344")
      (value "C")
      (footprint "SMD_1210_CAPC3225X279N")
      (fields
        (field (name "DB_PART_NUMBER") "CAP000047355")
        (field (name "DB_VALUE") "220uF")
        (field (name "DB_TOLERANCE") "20%")
        (field (name "DB_VOLTAGE") "6.3V")
        (field (name "DB_MANUFACTURER_PART") "SAMSUNG    CL32A227MQVNNNE")
        (field (name "DB_APPROVED_BY") "VSN")
      )
      (libsource (lib "Database_Libs1") (part "C"))
    )
    (comp (ref "C345")
      (value "C")
      (footprint "SMD_1210_CAPC3225X279N")
      (fields
        (field (name "DB_PART_NUMBER") "CAP000047355")
        (field (name "DB_VALUE") "220uF")
        (field (name "DB_TOLERANCE") "20%")
        (field (name "DB_VOLTAGE") "6.3V")
        (field (name "DB_MANUFACTURER_PART") "SAMSUNG    CL32A227MQVNNNE")
        (field (name "DB_APPROVED_BY") "VSN")
      )
      (libsource (lib "Database_Libs1") (part "C"))
    )
    (comp (ref "C346")
      (value "C")
      (footprint "SMD_1210_CAPC3225X279N")
      (fields
        (field (name "DB_PART_NUMBER") "CAP000047355")
        (field (name "DB_VALUE") "220uF")
        (field (name "DB_TOLERANCE") "20%")
        (field (name "DB_VOLTAGE") "6.3V")
        (field (name "DB_MANUFACTURER_PART") "SAMSUNG    CL32A227MQVNNNE")
        (field (name "DB_APPROVED_BY") "VSN")
      )
      (libsource (lib "Database_Libs1") (part "C"))
    )
    (comp (ref "U2")
      (value "Goldstrike1")
      (footprint "SMD_BGA1296C100P36X36")
      (libsource (lib "Schlib1") (part "Goldstrike1"))
    )
  )
  (nets
    (net (code "1") (name "1V") (class "Default")
      (node (ref "C267") (pin "2") (pinfunction "2_2") (pintype "passive"))
      (node (ref "C268") (pin "2") (pinfunction "2_2") (pintype "passive"))
      (node (ref "C269") (pin "2") (pinfunction "2_2") (pintype "passive"))
      (node (ref "C270") (pin "2") (pinfunction "2_2") (pintype "passive"))
      (node (ref "C271") (pin "2") (pinfunction "2_2") (pintype "passive"))
      (node (ref "C272") (pin "2") (pinfunction "2_2") (pintype "passive"))
      (node (ref "C273") (pin "2") (pinfunction "2_2") (pintype "passive"))
      (node (ref "C274") (pin "2") (pinfunction "2_2") (pintype "passive"))
      (node (ref "C275") (pin "2") (pinfunction "2_2") (pintype "passive"))
      (node (ref "C276") (pin "2") (pinfunction "2_2") (pintype "passive"))
      (node (ref "C277") (pin "2") (pinfunction "2_2") (pintype "passive"))
      (node (ref "C278") (pin "2") (pinfunction "2_2") (pintype "passive"))
      (node (ref "C279") (pin "2") (pinfunction "2_2") (pintype "passive"))
      (node (ref "C280") (pin "2") (pinfunction "2_2") (pintype "passive"))
      (node (ref "C281") (pin "2") (pinfunction "2_2") (pintype "passive"))
      (node (ref "C282") (pin "2") (pinfunction "2_2") (pintype "passive"))
      (node (ref "C283") (pin "2") (pinfunction "2_2") (pintype "passive"))
      (node (ref "C284") (pin "2") (pinfunction "2_2") (pintype "passive"))
      (node (ref "C285") (pin "2") (pinfunction "2_2") (pintype "passive"))
      (node (ref "C286") (pin "2") (pinfunction "2_2") (pintype "passive"))
      (node (ref "C287") (pin "2") (pinfunction "2_2") (pintype "passive"))
      (node (ref "C288") (pin "2") (pinfunction "2_2") (pintype "passive"))
      (node (ref "C289") (pin "2") (pinfunction "2_2") (pintype "passive"))
      (node (ref "C290") (pin "2") (pinfunction "2_2") (pintype "passive"))
      (node (ref "C291") (pin "2") (pinfunction "2_2") (pintype "passive"))
      (node (ref "C292") (pin "2") (pinfunction "2_2") (pintype "passive"))
      (node (ref "C293") (pin "2") (pinfunction "2_2") (pintype "passive"))
      (node (ref "C294") (pin "2") (pinfunction "2_2") (pintype "passive"))
      (node (ref "C295") (pin "2") (pinfunction "2_2") (pintype "passive"))
      (node (ref "C296") (pin "2") (pinfunction "2_2") (pintype "passive"))
      (node (ref "C297") (pin "2") (pinfunction "2_2") (pintype "passive"))
      (node (ref "C298") (pin "2") (pinfunction "2_2") (pintype "passive"))
      (node (ref "C299") (pin "2") (pinfunction "2_2") (pintype "passive"))
      (node (ref "C300") (pin "2") (pinfunction "2_2") (pintype "passive"))
      (node (ref "C301") (pin "2") (pinfunction "2_2") (pintype "passive"))
      (node (ref "C302") (pin "2") (pinfunction "2_2") (pintype "passive"))
      (node (ref "C303") (pin "2") (pinfunction "2_2") (pintype "passive"))
      (node (ref "C304") (pin "2") (pinfunction "2_2") (pintype "passive"))
      (node (ref "C305") (pin "2") (pinfunction "2_2") (pintype "passive"))
      (node (ref "C306") (pin "2") (pinfunction "2_2") (pintype "passive"))
      (node (ref "C307") (pin "2") (pinfunction "2_2") (pintype "passive"))
      (node (ref "C308") (pin "2") (pinfunction "2_2") (pintype "passive"))
      (node (ref "C309") (pin "2") (pinfunction "2_2") (pintype "passive"))
      (node (ref "C310") (pin "2") (pinfunction "2_2") (pintype "passive"))
      (node (ref "C311") (pin "2") (pinfunction "2_2") (pintype "passive"))
      (node (ref "C312") (pin "2") (pinfunction "2_2") (pintype "passive"))
      (node (ref "C313") (pin "2") (pinfunction "2_2") (pintype "passive"))
      (node (ref "C314") (pin "2") (pinfunction "2_2") (pintype "passive"))
      (node (ref "C315") (pin "2") (pinfunction "2_2") (pintype "passive"))
      (node (ref "C316") (pin "2") (pinfunction "2_2") (pintype "passive"))
      (node (ref "C317") (pin "2") (pinfunction "2_2") (pintype "passive"))
      (node (ref "C318") (pin "2") (pinfunction "2_2") (pintype "passive"))
      (node (ref "C319") (pin "2") (pinfunction "2_2") (pintype "passive"))
      (node (ref "C320") (pin "2") (pinfunction "2_2") (pintype "passive"))
      (node (ref "C321") (pin "2") (pinfunction "2_2") (pintype "passive"))
      (node (ref "C322") (pin "2") (pinfunction "2_2") (pintype "passive"))
      (node (ref "C323") (pin "2") (pinfunction "2_2") (pintype "passive"))
      (node (ref "C324") (pin "2") (pinfunction "2_2") (pintype "passive"))
      (node (ref "C325") (pin "2") (pinfunction "2_2") (pintype "passive"))
      (node (ref "C326") (pin "2") (pinfunction "2_2") (pintype "passive"))
      (node (ref "C327") (pin "2") (pinfunction "2_2") (pintype "passive"))
      (node (ref "C328") (pin "2") (pinfunction "2_2") (pintype "passive"))
      (node (ref "C329") (pin "2") (pinfunction "2_2") (pintype "passive"))
      (node (ref "C330") (pin "2") (pinfunction "2_2") (pintype "passive"))
      (node (ref "C331") (pin "2") (pinfunction "2_2") (pintype "passive"))
      (node (ref "C332") (pin "2") (pinfunction "2_2") (pintype "passive"))
      (node (ref "C333") (pin "2") (pinfunction "2_2") (pintype "passive"))
      (node (ref "C334") (pin "2") (pinfunction "2_2") (pintype "passive"))
      (node (ref "C335") (pin "2") (pinfunction "2_2") (pintype "passive"))
      (node (ref "C336") (pin "2") (pinfunction "2_2") (pintype "passive"))
      (node (ref "C337") (pin "2") (pinfunction "2_2") (pintype "passive"))
      (node (ref "C338") (pin "2") (pinfunction "2_2") (pintype "passive"))
      (node (ref "C339") (pin "2") (pinfunction "2_2") (pintype "passive"))
      (node (ref "C340") (pin "2") (pinfunction "2_2") (pintype "passive"))
      (node (ref "C341") (pin "2") (pinfunction "2_2") (pintype "passive"))
      (node (ref "C342") (pin "2") (pinfunction "2_2") (pintype "passive"))
      (node (ref "C343") (pin "2") (pinfunction "2_2") (pintype "passive"))
      (node (ref "C344") (pin "2") (pinfunction "2_2") (pintype "passive"))
      (node (ref "C345") (pin "2") (pinfunction "2_2") (pintype "passive"))
      (node (ref "C346") (pin "2") (pinfunction "2_2") (pintype "passive"))
      (node (ref "U2") (pin "A11") (pinfunction "VDD_TOP_4_A11") (pintype "passive"))
      (node (ref "U2") (pin "AA10") (pinfunction "VDD_TOP_1_AA10") (pintype "passive"))
      (node (ref "U2") (pin "AA12") (pinfunction "VDD_TOP_1_AA12") (pintype "passive"))
      (node (ref "U2") (pin "AA14") (pinfunction "VDD_TOP_1_AA14") (pintype "passive"))
      (node (ref "U2") (pin "AA16") (pinfunction "VDD_TOP_1_AA16") (pintype "passive"))
      (node (ref "U2") (pin "AA18") (pinfunction "VDD_TOP_1_AA18") (pintype "passive"))
      (node (ref "U2") (pin "AA19") (pinfunction "VDD_TOP_2_AA19") (pintype "passive"))
      (node (ref "U2") (pin "AA21") (pinfunction "VDD_TOP_2_AA21") (pintype "passive"))
      (node (ref "U2") (pin "AA23") (pinfunction "VDD_TOP_2_AA23") (pintype "passive"))
      (node (ref "U2") (pin "AA25") (pinfunction "VDD_TOP_2_AA25") (pintype "passive"))
      (node (ref "U2") (pin "AA27") (pinfunction "VDD_TOP_2_AA27") (pintype "passive"))
      (node (ref "U2") (pin "AA29") (pinfunction "VDD_TOP_2_AA29") (pintype "passive"))
      (node (ref "U2") (pin "AA31") (pinfunction "VDD_TOP_2_AA31") (pintype "passive"))
      (node (ref "U2") (pin "AA6") (pinfunction "VDD_TOP_1_AA6") (pintype "passive"))
      (node (ref "U2") (pin "AA8") (pinfunction "VDD_TOP_1_AA8") (pintype "passive"))
      (node (ref "U2") (pin "AB11") (pinfunction "VDD_TOP_1_AB11") (pintype "passive"))
      (node (ref "U2") (pin "AB13") (pinfunction "VDD_TOP_1_AB13") (pintype "passive"))
      (node (ref "U2") (pin "AB15") (pinfunction "VDD_TOP_1_AB15") (pintype "passive"))
      (node (ref "U2") (pin "AB17") (pinfunction "VDD_TOP_1_AB17") (pintype "passive"))
      (node (ref "U2") (pin "AB20") (pinfunction "VDD_TOP_2_AB20") (pintype "passive"))
      (node (ref "U2") (pin "AB22") (pinfunction "VDD_TOP_2_AB22") (pintype "passive"))
      (node (ref "U2") (pin "AB24") (pinfunction "VDD_TOP_2_AB24") (pintype "passive"))
      (node (ref "U2") (pin "AB26") (pinfunction "VDD_TOP_2_AB26") (pintype "passive"))
      (node (ref "U2") (pin "AB28") (pinfunction "VDD_TOP_2_AB28") (pintype "passive"))
      (node (ref "U2") (pin "AB30") (pinfunction "VDD_TOP_2_AB30") (pintype "passive"))
      (node (ref "U2") (pin "AB32") (pinfunction "VDD_TOP_2_AB32") (pintype "passive"))
      (node (ref "U2") (pin "AB7") (pinfunction "VDD_TOP_1_AB7") (pintype "passive"))
      (node (ref "U2") (pin "AB9") (pinfunction "VDD_TOP_1_AB9") (pintype "passive"))
      (node (ref "U2") (pin "AC10") (pinfunction "VDD_TOP_1_AC10") (pintype "passive"))
      (node (ref "U2") (pin "AC12") (pinfunction "VDD_TOP_1_AC12") (pintype "passive"))
      (node (ref "U2") (pin "AC14") (pinfunction "VDD_TOP_1_AC14") (pintype "passive"))
      (node (ref "U2") (pin "AC16") (pinfunction "VDD_TOP_1_AC16") (pintype "passive"))
      (node (ref "U2") (pin "AC18") (pinfunction "VDD_TOP_1_AC18") (pintype "passive"))
      (node (ref "U2") (pin "AC19") (pinfunction "VDD_TOP_2_AC19") (pintype "passive"))
      (node (ref "U2") (pin "AC21") (pinfunction "VDD_TOP_2_AC21") (pintype "passive"))
      (node (ref "U2") (pin "AC23") (pinfunction "VDD_TOP_2_AC23") (pintype "passive"))
      (node (ref "U2") (pin "AC25") (pinfunction "VDD_TOP_2_AC25") (pintype "passive"))
      (node (ref "U2") (pin "AC27") (pinfunction "VDD_TOP_2_AC27") (pintype "passive"))
      (node (ref "U2") (pin "AC29") (pinfunction "VDD_TOP_2_AC29") (pintype "passive"))
      (node (ref "U2") (pin "AC31") (pinfunction "VDD_TOP_2_AC31") (pintype "passive"))
      (node (ref "U2") (pin "AC6") (pinfunction "VDD_TOP_1_AC6") (pintype "passive"))
      (node (ref "U2") (pin "AC8") (pinfunction "VDD_TOP_1_AC8") (pintype "passive"))
      (node (ref "U2") (pin "AD11") (pinfunction "VDD_TOP_1_AD11") (pintype "passive"))
      (node (ref "U2") (pin "AD13") (pinfunction "VDD_TOP_1_AD13") (pintype "passive"))
      (node (ref "U2") (pin "AD15") (pinfunction "VDD_TOP_1_AD15") (pintype "passive"))
      (node (ref "U2") (pin "AD17") (pinfunction "VDD_TOP_1_AD17") (pintype "passive"))
      (node (ref "U2") (pin "AD20") (pinfunction "VDD_TOP_2_AD20") (pintype "passive"))
      (node (ref "U2") (pin "AD22") (pinfunction "VDD_TOP_2_AD22") (pintype "passive"))
      (node (ref "U2") (pin "AD24") (pinfunction "VDD_TOP_2_AD24") (pintype "passive"))
      (node (ref "U2") (pin "AD26") (pinfunction "VDD_TOP_2_AD26") (pintype "passive"))
      (node (ref "U2") (pin "AD28") (pinfunction "VDD_TOP_2_AD28") (pintype "passive"))
      (node (ref "U2") (pin "AD30") (pinfunction "VDD_TOP_2_AD30") (pintype "passive"))
      (node (ref "U2") (pin "AD32") (pinfunction "VDD_TOP_2_AD32") (pintype "passive"))
      (node (ref "U2") (pin "AD5") (pinfunction "VDD_TOP_1_AD5") (pintype "passive"))
      (node (ref "U2") (pin "AD7") (pinfunction "VDD_TOP_1_AD7") (pintype "passive"))
      (node (ref "U2") (pin "AD9") (pinfunction "VDD_TOP_1_AD9") (pintype "passive"))
      (node (ref "U2") (pin "AE10") (pinfunction "VDD_TOP_1_AE10") (pintype "passive"))
      (node (ref "U2") (pin "AE12") (pinfunction "VDD_TOP_1_AE12") (pintype "passive"))
      (node (ref "U2") (pin "AE14") (pinfunction "VDD_TOP_1_AE14") (pintype "passive"))
      (node (ref "U2") (pin "AE16") (pinfunction "VDD_TOP_1_AE16") (pintype "passive"))
      (node (ref "U2") (pin "AE18") (pinfunction "VDD_TOP_1_AE18") (pintype "passive"))
      (node (ref "U2") (pin "AE19") (pinfunction "VDD_TOP_2_AE19") (pintype "passive"))
      (node (ref "U2") (pin "AE21") (pinfunction "VDD_TOP_2_AE21") (pintype "passive"))
      (node (ref "U2") (pin "AE23") (pinfunction "VDD_TOP_2_AE23") (pintype "passive"))
      (node (ref "U2") (pin "AE25") (pinfunction "VDD_TOP_2_AE25") (pintype "passive"))
      (node (ref "U2") (pin "AE27") (pinfunction "VDD_TOP_2_AE27") (pintype "passive"))
      (node (ref "U2") (pin "AE29") (pinfunction "VDD_TOP_2_AE29") (pintype "passive"))
      (node (ref "U2") (pin "AE31") (pinfunction "VDD_TOP_2_AE31") (pintype "passive"))
      (node (ref "U2") (pin "AE6") (pinfunction "VDD_TOP_1_AE6") (pintype "passive"))
      (node (ref "U2") (pin "AE8") (pinfunction "VDD_TOP_1_AE8") (pintype "passive"))
      (node (ref "U2") (pin "AF1") (pinfunction "VDD_TOP_1_AF1") (pintype "passive"))
      (node (ref "U2") (pin "AF11") (pinfunction "VDD_TOP_1_AF11") (pintype "passive"))
      (node (ref "U2") (pin "AF13") (pinfunction "VDD_TOP_1_AF13") (pintype "passive"))
      (node (ref "U2") (pin "AF15") (pinfunction "VDD_TOP_1_AF15") (pintype "passive"))
      (node (ref "U2") (pin "AF17") (pinfunction "VDD_TOP_1_AF17") (pintype "passive"))
      (node (ref "U2") (pin "AF20") (pinfunction "VDD_TOP_2_AF20") (pintype "passive"))
      (node (ref "U2") (pin "AF22") (pinfunction "VDD_TOP_2_AF22") (pintype "passive"))
      (node (ref "U2") (pin "AF24") (pinfunction "VDD_TOP_2_AF24") (pintype "passive"))
      (node (ref "U2") (pin "AF26") (pinfunction "VDD_TOP_2_AF26") (pintype "passive"))
      (node (ref "U2") (pin "AF28") (pinfunction "VDD_TOP_2_AF28") (pintype "passive"))
      (node (ref "U2") (pin "AF30") (pinfunction "VDD_TOP_2_AF30") (pintype "passive"))
      (node (ref "U2") (pin "AF32") (pinfunction "VDD_TOP_2_AF32") (pintype "passive"))
      (node (ref "U2") (pin "AF7") (pinfunction "VDD_TOP_1_AF7") (pintype "passive"))
      (node (ref "U2") (pin "AF9") (pinfunction "VDD_TOP_1_AF9") (pintype "passive"))
      (node (ref "U2") (pin "AG10") (pinfunction "VDD_TOP_1_AG10") (pintype "passive"))
      (node (ref "U2") (pin "AG12") (pinfunction "VDD_TOP_1_AG12") (pintype "passive"))
      (node (ref "U2") (pin "AG14") (pinfunction "VDD_TOP_1_AG14") (pintype "passive"))
      (node (ref "U2") (pin "AG16") (pinfunction "VDD_TOP_1_AG16") (pintype "passive"))
      (node (ref "U2") (pin "AG18") (pinfunction "VDD_TOP_1_AG18") (pintype "passive"))
      (node (ref "U2") (pin "AG19") (pinfunction "VDD_TOP_2_AG19") (pintype "passive"))
      (node (ref "U2") (pin "AG21") (pinfunction "VDD_TOP_2_AG21") (pintype "passive"))
      (node (ref "U2") (pin "AG23") (pinfunction "VDD_TOP_2_AG23") (pintype "passive"))
      (node (ref "U2") (pin "AG25") (pinfunction "VDD_TOP_2_AG25") (pintype "passive"))
      (node (ref "U2") (pin "AG27") (pinfunction "VDD_TOP_2_AG27") (pintype "passive"))
      (node (ref "U2") (pin "AG29") (pinfunction "VDD_TOP_2_AG29") (pintype "passive"))
      (node (ref "U2") (pin "AG31") (pinfunction "VDD_TOP_2_AG31") (pintype "passive"))
      (node (ref "U2") (pin "AG6") (pinfunction "VDD_TOP_1_AG6") (pintype "passive"))
      (node (ref "U2") (pin "AG8") (pinfunction "VDD_TOP_1_AG8") (pintype "passive"))
      (node (ref "U2") (pin "AH11") (pinfunction "VDD_TOP_1_AH11") (pintype "passive"))
      (node (ref "U2") (pin "AH13") (pinfunction "VDD_TOP_1_AH13") (pintype "passive"))
      (node (ref "U2") (pin "AH15") (pinfunction "VDD_TOP_1_AH15") (pintype "passive"))
      (node (ref "U2") (pin "AH17") (pinfunction "VDD_TOP_1_AH17") (pintype "passive"))
      (node (ref "U2") (pin "AH20") (pinfunction "VDD_TOP_2_AH20") (pintype "passive"))
      (node (ref "U2") (pin "AH22") (pinfunction "VDD_TOP_2_AH22") (pintype "passive"))
      (node (ref "U2") (pin "AH24") (pinfunction "VDD_TOP_2_AH24") (pintype "passive"))
      (node (ref "U2") (pin "AH26") (pinfunction "VDD_TOP_2_AH26") (pintype "passive"))
      (node (ref "U2") (pin "AH28") (pinfunction "VDD_TOP_2_AH28") (pintype "passive"))
      (node (ref "U2") (pin "AH30") (pinfunction "VDD_TOP_2_AH30") (pintype "passive"))
      (node (ref "U2") (pin "AH32") (pinfunction "VDD_TOP_2_AH32") (pintype "passive"))
      (node (ref "U2") (pin "AH5") (pinfunction "VDD_TOP_1_AH5") (pintype "passive"))
      (node (ref "U2") (pin "AH7") (pinfunction "VDD_TOP_1_AH7") (pintype "passive"))
      (node (ref "U2") (pin "AH9") (pinfunction "VDD_TOP_1_AH9") (pintype "passive"))
      (node (ref "U2") (pin "AJ10") (pinfunction "VDD_TOP_1_AJ10") (pintype "passive"))
      (node (ref "U2") (pin "AJ12") (pinfunction "VDD_TOP_1_AJ12") (pintype "passive"))
      (node (ref "U2") (pin "AJ14") (pinfunction "VDD_TOP_1_AJ14") (pintype "passive"))
      (node (ref "U2") (pin "AJ16") (pinfunction "VDD_TOP_1_AJ16") (pintype "passive"))
      (node (ref "U2") (pin "AJ18") (pinfunction "VDD_TOP_1_AJ18") (pintype "passive"))
      (node (ref "U2") (pin "AJ19") (pinfunction "VDD_TOP_2_AJ19") (pintype "passive"))
      (node (ref "U2") (pin "AJ21") (pinfunction "VDD_TOP_2_AJ21") (pintype "passive"))
      (node (ref "U2") (pin "AJ23") (pinfunction "VDD_TOP_2_AJ23") (pintype "passive"))
      (node (ref "U2") (pin "AJ25") (pinfunction "VDD_TOP_2_AJ25") (pintype "passive"))
      (node (ref "U2") (pin "AJ27") (pinfunction "VDD_TOP_2_AJ27") (pintype "passive"))
      (node (ref "U2") (pin "AJ29") (pinfunction "VDD_TOP_2_AJ29") (pintype "passive"))
      (node (ref "U2") (pin "AJ31") (pinfunction "VDD_TOP_2_AJ31") (pintype "passive"))
      (node (ref "U2") (pin "AJ6") (pinfunction "VDD_TOP_1_AJ6") (pintype "passive"))
      (node (ref "U2") (pin "AJ8") (pinfunction "VDD_TOP_1_AJ8") (pintype "passive"))
      (node (ref "U2") (pin "AK11") (pinfunction "VDD_TOP_1_AK11") (pintype "passive"))
      (node (ref "U2") (pin "AK13") (pinfunction "VDD_TOP_1_AK13") (pintype "passive"))
      (node (ref "U2") (pin "AK15") (pinfunction "VDD_TOP_1_AK15") (pintype "passive"))
      (node (ref "U2") (pin "AK17") (pinfunction "VDD_TOP_1_AK17") (pintype "passive"))
      (node (ref "U2") (pin "AK20") (pinfunction "VDD_TOP_2_AK20") (pintype "passive"))
      (node (ref "U2") (pin "AK22") (pinfunction "VDD_TOP_2_AK22") (pintype "passive"))
      (node (ref "U2") (pin "AK24") (pinfunction "VDD_TOP_2_AK24") (pintype "passive"))
      (node (ref "U2") (pin "AK26") (pinfunction "VDD_TOP_2_AK26") (pintype "passive"))
      (node (ref "U2") (pin "AK28") (pinfunction "VDD_TOP_2_AK28") (pintype "passive"))
      (node (ref "U2") (pin "AK30") (pinfunction "VDD_TOP_2_AK30") (pintype "passive"))
      (node (ref "U2") (pin "AK5") (pinfunction "VDD_TOP_1_AK5") (pintype "passive"))
      (node (ref "U2") (pin "AK7") (pinfunction "VDD_TOP_1_AK7") (pintype "passive"))
      (node (ref "U2") (pin "AK9") (pinfunction "VDD_TOP_1_AK9") (pintype "passive"))
      (node (ref "U2") (pin "AL10") (pinfunction "VDD_TOP_1_AL10") (pintype "passive"))
      (node (ref "U2") (pin "AL12") (pinfunction "VDD_TOP_1_AL12") (pintype "passive"))
      (node (ref "U2") (pin "AL14") (pinfunction "VDD_TOP_1_AL14") (pintype "passive"))
      (node (ref "U2") (pin "AL16") (pinfunction "VDD_TOP_1_AL16") (pintype "passive"))
      (node (ref "U2") (pin "AL18") (pinfunction "VDD_TOP_1_AL18") (pintype "passive"))
      (node (ref "U2") (pin "AL19") (pinfunction "VDD_TOP_2_AL19") (pintype "passive"))
      (node (ref "U2") (pin "AL21") (pinfunction "VDD_TOP_2_AL21") (pintype "passive"))
      (node (ref "U2") (pin "AL23") (pinfunction "VDD_TOP_2_AL23") (pintype "passive"))
      (node (ref "U2") (pin "AL25") (pinfunction "VDD_TOP_2_AL25") (pintype "passive"))
      (node (ref "U2") (pin "AL27") (pinfunction "VDD_TOP_2_AL27") (pintype "passive"))
      (node (ref "U2") (pin "AL29") (pinfunction "VDD_TOP_2_AL29") (pintype "passive"))
      (node (ref "U2") (pin "AL31") (pinfunction "VDD_TOP_2_AL31") (pintype "passive"))
      (node (ref "U2") (pin "AL6") (pinfunction "VDD_TOP_1_AL6") (pintype "passive"))
      (node (ref "U2") (pin "AL8") (pinfunction "VDD_TOP_1_AL8") (pintype "passive"))
      (node (ref "U2") (pin "AM11") (pinfunction "VDD_TOP_1_AM11") (pintype "passive"))
      (node (ref "U2") (pin "AM13") (pinfunction "VDD_TOP_1_AM13") (pintype "passive"))
      (node (ref "U2") (pin "AM15") (pinfunction "VDD_TOP_1_AM15") (pintype "passive"))
      (node (ref "U2") (pin "AM17") (pinfunction "VDD_TOP_1_AM17") (pintype "passive"))
      (node (ref "U2") (pin "AM24") (pinfunction "VDD_TOP_2_AM24") (pintype "passive"))
      (node (ref "U2") (pin "AM28") (pinfunction "VDD_TOP_2_AM28") (pintype "passive"))
      (node (ref "U2") (pin "AM30") (pinfunction "VDD_TOP_2_AM30") (pintype "passive"))
      (node (ref "U2") (pin "AM9") (pinfunction "VDD_TOP_1_AM9") (pintype "passive"))
      (node (ref "U2") (pin "AN18") (pinfunction "VDD_TOP_1_AN18") (pintype "passive"))
      (node (ref "U2") (pin "AT26") (pinfunction "VDD_TOP_2_AT26") (pintype "passive"))
      (node (ref "U2") (pin "D19") (pinfunction "VDD_TOP_3_D19") (pintype "passive"))
      (node (ref "U2") (pin "E13") (pinfunction "VDD_TOP_4_E13") (pintype "passive"))
      (node (ref "U2") (pin "E20") (pinfunction "VDD_TOP_3_E20") (pintype "passive"))
      (node (ref "U2") (pin "E22") (pinfunction "VDD_TOP_3_E22") (pintype "passive"))
      (node (ref "U2") (pin "E24") (pinfunction "VDD_TOP_3_E24") (pintype "passive"))
      (node (ref "U2") (pin "E26") (pinfunction "VDD_TOP_3_E26") (pintype "passive"))
      (node (ref "U2") (pin "E28") (pinfunction "VDD_TOP_3_E28") (pintype "passive"))
      (node (ref "U2") (pin "E7") (pinfunction "VDD_TOP_4_E7") (pintype "passive"))
      (node (ref "U2") (pin "E9") (pinfunction "VDD_TOP_4_E9") (pintype "passive"))
      (node (ref "U2") (pin "F10") (pinfunction "VDD_TOP_4_F10") (pintype "passive"))
      (node (ref "U2") (pin "F12") (pinfunction "VDD_TOP_4_F12") (pintype "passive"))
      (node (ref "U2") (pin "F14") (pinfunction "VDD_TOP_4_F14") (pintype "passive"))
      (node (ref "U2") (pin "F16") (pinfunction "VDD_TOP_4_F16") (pintype "passive"))
      (node (ref "U2") (pin "F18") (pinfunction "VDD_TOP_4_F18") (pintype "passive"))
      (node (ref "U2") (pin "F19") (pinfunction "VDD_TOP_3_F19") (pintype "passive"))
      (node (ref "U2") (pin "F21") (pinfunction "VDD_TOP_3_F21") (pintype "passive"))
      (node (ref "U2") (pin "F23") (pinfunction "VDD_TOP_3_F23") (pintype "passive"))
      (node (ref "U2") (pin "F25") (pinfunction "VDD_TOP_3_F25") (pintype "passive"))
      (node (ref "U2") (pin "F27") (pinfunction "VDD_TOP_3_F27") (pintype "passive"))
      (node (ref "U2") (pin "F29") (pinfunction "VDD_TOP_3_F29") (pintype "passive"))
      (node (ref "U2") (pin "F31") (pinfunction "VDD_TOP_3_F31") (pintype "passive"))
      (node (ref "U2") (pin "F6") (pinfunction "VDD_TOP_4_F6") (pintype "passive"))
      (node (ref "U2") (pin "F8") (pinfunction "VDD_TOP_4_F8") (pintype "passive"))
      (node (ref "U2") (pin "G11") (pinfunction "VDD_TOP_4_G11") (pintype "passive"))
      (node (ref "U2") (pin "G13") (pinfunction "VDD_TOP_4_G13") (pintype "passive"))
      (node (ref "U2") (pin "G15") (pinfunction "VDD_TOP_4_G15") (pintype "passive"))
      (node (ref "U2") (pin "G17") (pinfunction "VDD_TOP_4_G17") (pintype "passive"))
      (node (ref "U2") (pin "G20") (pinfunction "VDD_TOP_3_G20") (pintype "passive"))
      (node (ref "U2") (pin "G22") (pinfunction "VDD_TOP_3_G22") (pintype "passive"))
      (node (ref "U2") (pin "G24") (pinfunction "VDD_TOP_3_G24") (pintype "passive"))
      (node (ref "U2") (pin "G26") (pinfunction "VDD_TOP_3_G26") (pintype "passive"))
      (node (ref "U2") (pin "G28") (pinfunction "VDD_TOP_3_G28") (pintype "passive"))
      (node (ref "U2") (pin "G30") (pinfunction "VDD_TOP_3_G30") (pintype "passive"))
      (node (ref "U2") (pin "G32") (pinfunction "VDD_TOP_3_G32") (pintype "passive"))
      (node (ref "U2") (pin "G7") (pinfunction "VDD_TOP_4_G7") (pintype "passive"))
      (node (ref "U2") (pin "G9") (pinfunction "VDD_TOP_4_G9") (pintype "passive"))
      (node (ref "U2") (pin "H10") (pinfunction "VDD_TOP_4_H10") (pintype "passive"))
      (node (ref "U2") (pin "H12") (pinfunction "VDD_TOP_4_H12") (pintype "passive"))
      (node (ref "U2") (pin "H14") (pinfunction "VDD_TOP_4_H14") (pintype "passive"))
      (node (ref "U2") (pin "H16") (pinfunction "VDD_TOP_4_H16") (pintype "passive"))
      (node (ref "U2") (pin "H18") (pinfunction "VDD_TOP_4_H18") (pintype "passive"))
      (node (ref "U2") (pin "H19") (pinfunction "VDD_TOP_3_H19") (pintype "passive"))
      (node (ref "U2") (pin "H21") (pinfunction "VDD_TOP_3_H21") (pintype "passive"))
      (node (ref "U2") (pin "H23") (pinfunction "VDD_TOP_3_H23") (pintype "passive"))
      (node (ref "U2") (pin "H25") (pinfunction "VDD_TOP_3_H25") (pintype "passive"))
      (node (ref "U2") (pin "H27") (pinfunction "VDD_TOP_3_H27") (pintype "passive"))
      (node (ref "U2") (pin "H29") (pinfunction "VDD_TOP_3_H29") (pintype "passive"))
      (node (ref "U2") (pin "H31") (pinfunction "VDD_TOP_3_H31") (pintype "passive"))
      (node (ref "U2") (pin "H6") (pinfunction "VDD_TOP_4_H6") (pintype "passive"))
      (node (ref "U2") (pin "H8") (pinfunction "VDD_TOP_4_H8") (pintype "passive"))
      (node (ref "U2") (pin "J11") (pinfunction "VDD_TOP_4_J11") (pintype "passive"))
      (node (ref "U2") (pin "J13") (pinfunction "VDD_TOP_4_J13") (pintype "passive"))
      (node (ref "U2") (pin "J15") (pinfunction "VDD_TOP_4_J15") (pintype "passive"))
      (node (ref "U2") (pin "J17") (pinfunction "VDD_TOP_4_J17") (pintype "passive"))
      (node (ref "U2") (pin "J20") (pinfunction "VDD_TOP_3_J20") (pintype "passive"))
      (node (ref "U2") (pin "J22") (pinfunction "VDD_TOP_3_J22") (pintype "passive"))
      (node (ref "U2") (pin "J24") (pinfunction "VDD_TOP_3_J24") (pintype "passive"))
      (node (ref "U2") (pin "J26") (pinfunction "VDD_TOP_3_J26") (pintype "passive"))
      (node (ref "U2") (pin "J28") (pinfunction "VDD_TOP_3_J28") (pintype "passive"))
      (node (ref "U2") (pin "J30") (pinfunction "VDD_TOP_3_J30") (pintype "passive"))
      (node (ref "U2") (pin "J32") (pinfunction "VDD_TOP_3_J32") (pintype "passive"))
      (node (ref "U2") (pin "J5") (pinfunction "VDD_TOP_4_J5") (pintype "passive"))
      (node (ref "U2") (pin "J7") (pinfunction "VDD_TOP_4_J7") (pintype "passive"))
      (node (ref "U2") (pin "J9") (pinfunction "VDD_TOP_4_J9") (pintype "passive"))
      (node (ref "U2") (pin "K10") (pinfunction "VDD_TOP_4_K10") (pintype "passive"))
      (node (ref "U2") (pin "K12") (pinfunction "VDD_TOP_4_K12") (pintype "passive"))
      (node (ref "U2") (pin "K14") (pinfunction "VDD_TOP_4_K14") (pintype "passive"))
      (node (ref "U2") (pin "K16") (pinfunction "VDD_TOP_4_K16") (pintype "passive"))
      (node (ref "U2") (pin "K18") (pinfunction "VDD_TOP_4_K18") (pintype "passive"))
      (node (ref "U2") (pin "K19") (pinfunction "VDD_TOP_3_K19") (pintype "passive"))
      (node (ref "U2") (pin "K21") (pinfunction "VDD_TOP_3_K21") (pintype "passive"))
      (node (ref "U2") (pin "K23") (pinfunction "VDD_TOP_3_K23") (pintype "passive"))
      (node (ref "U2") (pin "K25") (pinfunction "VDD_TOP_3_K25") (pintype "passive"))
      (node (ref "U2") (pin "K27") (pinfunction "VDD_TOP_3_K27") (pintype "passive"))
      (node (ref "U2") (pin "K29") (pinfunction "VDD_TOP_3_K29") (pintype "passive"))
      (node (ref "U2") (pin "K31") (pinfunction "VDD_TOP_3_K31") (pintype "passive"))
      (node (ref "U2") (pin "K6") (pinfunction "VDD_TOP_4_K6") (pintype "passive"))
      (node (ref "U2") (pin "K8") (pinfunction "VDD_TOP_4_K8") (pintype "passive"))
      (node (ref "U2") (pin "L11") (pinfunction "VDD_TOP_4_L11") (pintype "passive"))
      (node (ref "U2") (pin "L13") (pinfunction "VDD_TOP_4_L13") (pintype "passive"))
      (node (ref "U2") (pin "L15") (pinfunction "VDD_TOP_4_L15") (pintype "passive"))
      (node (ref "U2") (pin "L17") (pinfunction "VDD_TOP_4_L17") (pintype "passive"))
      (node (ref "U2") (pin "L20") (pinfunction "VDD_TOP_3_L20") (pintype "passive"))
      (node (ref "U2") (pin "L22") (pinfunction "VDD_TOP_3_L22") (pintype "passive"))
      (node (ref "U2") (pin "L24") (pinfunction "VDD_TOP_3_L24") (pintype "passive"))
      (node (ref "U2") (pin "L26") (pinfunction "VDD_TOP_3_L26") (pintype "passive"))
      (node (ref "U2") (pin "L28") (pinfunction "VDD_TOP_3_L28") (pintype "passive"))
      (node (ref "U2") (pin "L30") (pinfunction "VDD_TOP_3_L30") (pintype "passive"))
      (node (ref "U2") (pin "L36") (pinfunction "VDD_TOP_3_L36") (pintype "passive"))
      (node (ref "U2") (pin "L5") (pinfunction "VDD_TOP_4_L5") (pintype "passive"))
      (node (ref "U2") (pin "L7") (pinfunction "VDD_TOP_4_L7") (pintype "passive"))
      (node (ref "U2") (pin "L9") (pinfunction "VDD_TOP_4_L9") (pintype "passive"))
      (node (ref "U2") (pin "M10") (pinfunction "VDD_TOP_4_M10") (pintype "passive"))
      (node (ref "U2") (pin "M12") (pinfunction "VDD_TOP_4_M12") (pintype "passive"))
      (node (ref "U2") (pin "M14") (pinfunction "VDD_TOP_4_M14") (pintype "passive"))
      (node (ref "U2") (pin "M16") (pinfunction "VDD_TOP_4_M16") (pintype "passive"))
      (node (ref "U2") (pin "M18") (pinfunction "VDD_TOP_4_M18") (pintype "passive"))
      (node (ref "U2") (pin "M19") (pinfunction "VDD_TOP_3_M19") (pintype "passive"))
      (node (ref "U2") (pin "M21") (pinfunction "VDD_TOP_3_M21") (pintype "passive"))
      (node (ref "U2") (pin "M23") (pinfunction "VDD_TOP_3_M23") (pintype "passive"))
      (node (ref "U2") (pin "M25") (pinfunction "VDD_TOP_3_M25") (pintype "passive"))
      (node (ref "U2") (pin "M27") (pinfunction "VDD_TOP_3_M27") (pintype "passive"))
      (node (ref "U2") (pin "M29") (pinfunction "VDD_TOP_3_M29") (pintype "passive"))
      (node (ref "U2") (pin "M31") (pinfunction "VDD_TOP_3_M31") (pintype "passive"))
      (node (ref "U2") (pin "M6") (pinfunction "VDD_TOP_4_M6") (pintype "passive"))
      (node (ref "U2") (pin "M8") (pinfunction "VDD_TOP_4_M8") (pintype "passive"))
      (node (ref "U2") (pin "N11") (pinfunction "VDD_TOP_4_N11") (pintype "passive"))
      (node (ref "U2") (pin "N13") (pinfunction "VDD_TOP_4_N13") (pintype "passive"))
      (node (ref "U2") (pin "N15") (pinfunction "VDD_TOP_4_N15") (pintype "passive"))
      (node (ref "U2") (pin "N17") (pinfunction "VDD_TOP_4_N17") (pintype "passive"))
      (node (ref "U2") (pin "N20") (pinfunction "VDD_TOP_3_N20") (pintype "passive"))
      (node (ref "U2") (pin "N22") (pinfunction "VDD_TOP_3_N22") (pintype "passive"))
      (node (ref "U2") (pin "N24") (pinfunction "VDD_TOP_3_N24") (pintype "passive"))
      (node (ref "U2") (pin "N26") (pinfunction "VDD_TOP_3_N26") (pintype "passive"))
      (node (ref "U2") (pin "N28") (pinfunction "VDD_TOP_3_N28") (pintype "passive"))
      (node (ref "U2") (pin "N30") (pinfunction "VDD_TOP_3_N30") (pintype "passive"))
      (node (ref "U2") (pin "N32") (pinfunction "VDD_TOP_3_N32") (pintype "passive"))
      (node (ref "U2") (pin "N5") (pinfunction "VDD_TOP_4_N5") (pintype "passive"))
      (node (ref "U2") (pin "N7") (pinfunction "VDD_TOP_4_N7") (pintype "passive"))
      (node (ref "U2") (pin "N9") (pinfunction "VDD_TOP_4_N9") (pintype "passive"))
      (node (ref "U2") (pin "P10") (pinfunction "VDD_TOP_4_P10") (pintype "passive"))
      (node (ref "U2") (pin "P12") (pinfunction "VDD_TOP_4_P12") (pintype "passive"))
      (node (ref "U2") (pin "P14") (pinfunction "VDD_TOP_4_P14") (pintype "passive"))
      (node (ref "U2") (pin "P16") (pinfunction "VDD_TOP_4_P16") (pintype "passive"))
      (node (ref "U2") (pin "P18") (pinfunction "VDD_TOP_4_P18") (pintype "passive"))
      (node (ref "U2") (pin "P19") (pinfunction "VDD_TOP_3_P19") (pintype "passive"))
      (node (ref "U2") (pin "P21") (pinfunction "VDD_TOP_3_P21") (pintype "passive"))
      (node (ref "U2") (pin "P23") (pinfunction "VDD_TOP_3_P23") (pintype "passive"))
      (node (ref "U2") (pin "P25") (pinfunction "VDD_TOP_3_P25") (pintype "passive"))
      (node (ref "U2") (pin "P27") (pinfunction "VDD_TOP_3_P27") (pintype "passive"))
      (node (ref "U2") (pin "P29") (pinfunction "VDD_TOP_3_P29") (pintype "passive"))
      (node (ref "U2") (pin "P31") (pinfunction "VDD_TOP_3_P31") (pintype "passive"))
      (node (ref "U2") (pin "P6") (pinfunction "VDD_TOP_4_P6") (pintype "passive"))
      (node (ref "U2") (pin "P8") (pinfunction "VDD_TOP_4_P8") (pintype "passive"))
      (node (ref "U2") (pin "R11") (pinfunction "VDD_TOP_4_R11") (pintype "passive"))
      (node (ref "U2") (pin "R13") (pinfunction "VDD_TOP_4_R13") (pintype "passive"))
      (node (ref "U2") (pin "R15") (pinfunction "VDD_TOP_4_R15") (pintype "passive"))
      (node (ref "U2") (pin "R17") (pinfunction "VDD_TOP_4_R17") (pintype "passive"))
      (node (ref "U2") (pin "R20") (pinfunction "VDD_TOP_3_R20") (pintype "passive"))
      (node (ref "U2") (pin "R22") (pinfunction "VDD_TOP_3_R22") (pintype "passive"))
      (node (ref "U2") (pin "R24") (pinfunction "VDD_TOP_3_R24") (pintype "passive"))
      (node (ref "U2") (pin "R26") (pinfunction "VDD_TOP_3_R26") (pintype "passive"))
      (node (ref "U2") (pin "R28") (pinfunction "VDD_TOP_3_R28") (pintype "passive"))
      (node (ref "U2") (pin "R30") (pinfunction "VDD_TOP_3_R30") (pintype "passive"))
      (node (ref "U2") (pin "R5") (pinfunction "VDD_TOP_4_R5") (pintype "passive"))
      (node (ref "U2") (pin "R7") (pinfunction "VDD_TOP_4_R7") (pintype "passive"))
      (node (ref "U2") (pin "R9") (pinfunction "VDD_TOP_4_R9") (pintype "passive"))
      (node (ref "U2") (pin "T10") (pinfunction "VDD_TOP_4_T10") (pintype "passive"))
      (node (ref "U2") (pin "T12") (pinfunction "VDD_TOP_4_T12") (pintype "passive"))
      (node (ref "U2") (pin "T14") (pinfunction "VDD_TOP_4_T14") (pintype "passive"))
      (node (ref "U2") (pin "T16") (pinfunction "VDD_TOP_4_T16") (pintype "passive"))
      (node (ref "U2") (pin "T18") (pinfunction "VDD_TOP_4_T18") (pintype "passive"))
      (node (ref "U2") (pin "T19") (pinfunction "VDD_TOP_3_T19") (pintype "passive"))
      (node (ref "U2") (pin "T21") (pinfunction "VDD_TOP_3_T21") (pintype "passive"))
      (node (ref "U2") (pin "T23") (pinfunction "VDD_TOP_3_T23") (pintype "passive"))
      (node (ref "U2") (pin "T25") (pinfunction "VDD_TOP_3_T25") (pintype "passive"))
      (node (ref "U2") (pin "T27") (pinfunction "VDD_TOP_3_T27") (pintype "passive"))
      (node (ref "U2") (pin "T29") (pinfunction "VDD_TOP_3_T29") (pintype "passive"))
      (node (ref "U2") (pin "T31") (pinfunction "VDD_TOP_3_T31") (pintype "passive"))
      (node (ref "U2") (pin "T6") (pinfunction "VDD_TOP_4_T6") (pintype "passive"))
      (node (ref "U2") (pin "T8") (pinfunction "VDD_TOP_4_T8") (pintype "passive"))
      (node (ref "U2") (pin "U11") (pinfunction "VDD_TOP_4_U11") (pintype "passive"))
      (node (ref "U2") (pin "U13") (pinfunction "VDD_TOP_4_U13") (pintype "passive"))
      (node (ref "U2") (pin "U15") (pinfunction "VDD_TOP_4_U15") (pintype "passive"))
      (node (ref "U2") (pin "U17") (pinfunction "VDD_TOP_4_U17") (pintype "passive"))
      (node (ref "U2") (pin "U20") (pinfunction "VDD_TOP_3_U20") (pintype "passive"))
      (node (ref "U2") (pin "U22") (pinfunction "VDD_TOP_3_U22") (pintype "passive"))
      (node (ref "U2") (pin "U24") (pinfunction "VDD_TOP_3_U24") (pintype "passive"))
      (node (ref "U2") (pin "U26") (pinfunction "VDD_TOP_3_U26") (pintype "passive"))
      (node (ref "U2") (pin "U28") (pinfunction "VDD_TOP_3_U28") (pintype "passive"))
      (node (ref "U2") (pin "U30") (pinfunction "VDD_TOP_3_U30") (pintype "passive"))
      (node (ref "U2") (pin "U5") (pinfunction "VDD_TOP_4_U5") (pintype "passive"))
      (node (ref "U2") (pin "U7") (pinfunction "VDD_TOP_4_U7") (pintype "passive"))
      (node (ref "U2") (pin "U9") (pinfunction "VDD_TOP_4_U9") (pintype "passive"))
      (node (ref "U2") (pin "V10") (pinfunction "VDD_TOP_4_V10") (pintype "passive"))
      (node (ref "U2") (pin "V12") (pinfunction "VDD_TOP_4_V12") (pintype "passive"))
      (node (ref "U2") (pin "V14") (pinfunction "VDD_TOP_4_V14") (pintype "passive"))
      (node (ref "U2") (pin "V16") (pinfunction "VDD_TOP_4_V16") (pintype "passive"))
      (node (ref "U2") (pin "V18") (pinfunction "VDD_TOP_4_V18") (pintype "passive"))
      (node (ref "U2") (pin "V19") (pinfunction "VDD_TOP_3_V19") (pintype "passive"))
      (node (ref "U2") (pin "V21") (pinfunction "VDD_TOP_3_V21") (pintype "passive"))
      (node (ref "U2") (pin "V23") (pinfunction "VDD_TOP_3_V23") (pintype "passive"))
      (node (ref "U2") (pin "V25") (pinfunction "VDD_TOP_3_V25") (pintype "passive"))
      (node (ref "U2") (pin "V27") (pinfunction "VDD_TOP_3_V27") (pintype "passive"))
      (node (ref "U2") (pin "V29") (pinfunction "VDD_TOP_3_V29") (pintype "passive"))
      (node (ref "U2") (pin "V31") (pinfunction "VDD_TOP_3_V31") (pintype "passive"))
      (node (ref "U2") (pin "V4") (pinfunction "VDD_TOP_4_V4") (pintype "passive"))
      (node (ref "U2") (pin "V6") (pinfunction "VDD_TOP_4_V6") (pintype "passive"))
      (node (ref "U2") (pin "V8") (pinfunction "VDD_TOP_4_V8") (pintype "passive"))
      (node (ref "U2") (pin "W10") (pinfunction "VDD_TOP_1_W10") (pintype "passive"))
      (node (ref "U2") (pin "W12") (pinfunction "VDD_TOP_1_W12") (pintype "passive"))
      (node (ref "U2") (pin "W14") (pinfunction "VDD_TOP_1_W14") (pintype "passive"))
      (node (ref "U2") (pin "W16") (pinfunction "VDD_TOP_1_W16") (pintype "passive"))
      (node (ref "U2") (pin "W18") (pinfunction "VDD_TOP_1_W18") (pintype "passive"))
      (node (ref "U2") (pin "W19") (pinfunction "VDD_TOP_2_W19") (pintype "passive"))
      (node (ref "U2") (pin "W21") (pinfunction "VDD_TOP_2_W21") (pintype "passive"))
      (node (ref "U2") (pin "W23") (pinfunction "VDD_TOP_2_W23") (pintype "passive"))
      (node (ref "U2") (pin "W25") (pinfunction "VDD_TOP_2_W25") (pintype "passive"))
      (node (ref "U2") (pin "W27") (pinfunction "VDD_TOP_2_W27") (pintype "passive"))
      (node (ref "U2") (pin "W29") (pinfunction "VDD_TOP_2_W29") (pintype "passive"))
      (node (ref "U2") (pin "W31") (pinfunction "VDD_TOP_2_W31") (pintype "passive"))
      (node (ref "U2") (pin "W33") (pinfunction "VDD_TOP_2_W33") (pintype "passive"))
      (node (ref "U2") (pin "W6") (pinfunction "VDD_TOP_1_W6") (pintype "passive"))
      (node (ref "U2") (pin "W8") (pinfunction "VDD_TOP_1_W8") (pintype "passive"))
      (node (ref "U2") (pin "Y11") (pinfunction "VDD_TOP_1_Y11") (pintype "passive"))
      (node (ref "U2") (pin "Y13") (pinfunction "VDD_TOP_1_Y13") (pintype "passive"))
      (node (ref "U2") (pin "Y15") (pinfunction "VDD_TOP_1_Y15") (pintype "passive"))
      (node (ref "U2") (pin "Y17") (pinfunction "VDD_TOP_1_Y17") (pintype "passive"))
      (node (ref "U2") (pin "Y20") (pinfunction "VDD_TOP_2_Y20") (pintype "passive"))
      (node (ref "U2") (pin "Y22") (pinfunction "VDD_TOP_2_Y22") (pintype "passive"))
      (node (ref "U2") (pin "Y24") (pinfunction "VDD_TOP_2_Y24") (pintype "passive"))
      (node (ref "U2") (pin "Y26") (pinfunction "VDD_TOP_2_Y26") (pintype "passive"))
      (node (ref "U2") (pin "Y28") (pinfunction "VDD_TOP_2_Y28") (pintype "passive"))
      (node (ref "U2") (pin "Y30") (pinfunction "VDD_TOP_2_Y30") (pintype "passive"))
      (node (ref "U2") (pin "Y32") (pinfunction "VDD_TOP_2_Y32") (pintype "passive"))
      (node (ref "U2") (pin "Y7") (pinfunction "VDD_TOP_1_Y7") (pintype "passive"))
      (node (ref "U2") (pin "Y9") (pinfunction "VDD_TOP_1_Y9") (pintype "passive"))
    )
    (net (code "2") (name "GND") (class "Default")
      (node (ref "C267") (pin "1") (pinfunction "1_1") (pintype "passive"))
      (node (ref "C268") (pin "1") (pinfunction "1_1") (pintype "passive"))
      (node (ref "C269") (pin "1") (pinfunction "1_1") (pintype "passive"))
      (node (ref "C270") (pin "1") (pinfunction "1_1") (pintype "passive"))
      (node (ref "C271") (pin "1") (pinfunction "1_1") (pintype "passive"))
      (node (ref "C272") (pin "1") (pinfunction "1_1") (pintype "passive"))
      (node (ref "C273") (pin "1") (pinfunction "1_1") (pintype "passive"))
      (node (ref "C274") (pin "1") (pinfunction "1_1") (pintype "passive"))
      (node (ref "C275") (pin "1") (pinfunction "1_1") (pintype "passive"))
      (node (ref "C276") (pin "1") (pinfunction "1_1") (pintype "passive"))
      (node (ref "C277") (pin "1") (pinfunction "1_1") (pintype "passive"))
      (node (ref "C278") (pin "1") (pinfunction "1_1") (pintype "passive"))
      (node (ref "C279") (pin "1") (pinfunction "1_1") (pintype "passive"))
      (node (ref "C280") (pin "1") (pinfunction "1_1") (pintype "passive"))
      (node (ref "C281") (pin "1") (pinfunction "1_1") (pintype "passive"))
      (node (ref "C282") (pin "1") (pinfunction "1_1") (pintype "passive"))
      (node (ref "C283") (pin "1") (pinfunction "1_1") (pintype "passive"))
      (node (ref "C284") (pin "1") (pinfunction "1_1") (pintype "passive"))
      (node (ref "C285") (pin "1") (pinfunction "1_1") (pintype "passive"))
      (node (ref "C286") (pin "1") (pinfunction "1_1") (pintype "passive"))
      (node (ref "C287") (pin "1") (pinfunction "1_1") (pintype "passive"))
      (node (ref "C288") (pin "1") (pinfunction "1_1") (pintype "passive"))
      (node (ref "C289") (pin "1") (pinfunction "1_1") (pintype "passive"))
      (node (ref "C290") (pin "1") (pinfunction "1_1") (pintype "passive"))
      (node (ref "C291") (pin "1") (pinfunction "1_1") (pintype "passive"))
      (node (ref "C292") (pin "1") (pinfunction "1_1") (pintype "passive"))
      (node (ref "C293") (pin "1") (pinfunction "1_1") (pintype "passive"))
      (node (ref "C294") (pin "1") (pinfunction "1_1") (pintype "passive"))
      (node (ref "C295") (pin "1") (pinfunction "1_1") (pintype "passive"))
      (node (ref "C296") (pin "1") (pinfunction "1_1") (pintype "passive"))
      (node (ref "C297") (pin "1") (pinfunction "1_1") (pintype "passive"))
      (node (ref "C298") (pin "1") (pinfunction "1_1") (pintype "passive"))
      (node (ref "C299") (pin "1") (pinfunction "1_1") (pintype "passive"))
      (node (ref "C300") (pin "1") (pinfunction "1_1") (pintype "passive"))
      (node (ref "C301") (pin "1") (pinfunction "1_1") (pintype "passive"))
      (node (ref "C302") (pin "1") (pinfunction "1_1") (pintype "passive"))
      (node (ref "C303") (pin "1") (pinfunction "1_1") (pintype "passive"))
      (node (ref "C304") (pin "1") (pinfunction "1_1") (pintype "passive"))
      (node (ref "C305") (pin "1") (pinfunction "1_1") (pintype "passive"))
      (node (ref "C306") (pin "1") (pinfunction "1_1") (pintype "passive"))
      (node (ref "C307") (pin "1") (pinfunction "1_1") (pintype "passive"))
      (node (ref "C308") (pin "1") (pinfunction "1_1") (pintype "passive"))
      (node (ref "C309") (pin "1") (pinfunction "1_1") (pintype "passive"))
      (node (ref "C310") (pin "1") (pinfunction "1_1") (pintype "passive"))
      (node (ref "C311") (pin "1") (pinfunction "1_1") (pintype "passive"))
      (node (ref "C312") (pin "1") (pinfunction "1_1") (pintype "passive"))
      (node (ref "C313") (pin "1") (pinfunction "1_1") (pintype "passive"))
      (node (ref "C314") (pin "1") (pinfunction "1_1") (pintype "passive"))
      (node (ref "C315") (pin "1") (pinfunction "1_1") (pintype "passive"))
      (node (ref "C316") (pin "1") (pinfunction "1_1") (pintype "passive"))
      (node (ref "C317") (pin "1") (pinfunction "1_1") (pintype "passive"))
      (node (ref "C318") (pin "1") (pinfunction "1_1") (pintype "passive"))
      (node (ref "C319") (pin "1") (pinfunction "1_1") (pintype "passive"))
      (node (ref "C320") (pin "1") (pinfunction "1_1") (pintype "passive"))
      (node (ref "C321") (pin "1") (pinfunction "1_1") (pintype "passive"))
      (node (ref "C322") (pin "1") (pinfunction "1_1") (pintype "passive"))
      (node (ref "C323") (pin "1") (pinfunction "1_1") (pintype "passive"))
      (node (ref "C324") (pin "1") (pinfunction "1_1") (pintype "passive"))
      (node (ref "C325") (pin "1") (pinfunction "1_1") (pintype "passive"))
      (node (ref "C326") (pin "1") (pinfunction "1_1") (pintype "passive"))
      (node (ref "C327") (pin "1") (pinfunction "1_1") (pintype "passive"))
      (node (ref "C328") (pin "1") (pinfunction "1_1") (pintype "passive"))
      (node (ref "C329") (pin "1") (pinfunction "1_1") (pintype "passive"))
      (node (ref "C330") (pin "1") (pinfunction "1_1") (pintype "passive"))
      (node (ref "C331") (pin "1") (pinfunction "1_1") (pintype "passive"))
      (node (ref "C332") (pin "1") (pinfunction "1_1") (pintype "passive"))
      (node (ref "C333") (pin "1") (pinfunction "1_1") (pintype "passive"))
      (node (ref "C334") (pin "1") (pinfunction "1_1") (pintype "passive"))
      (node (ref "C335") (pin "1") (pinfunction "1_1") (pintype "passive"))
      (node (ref "C336") (pin "1") (pinfunction "1_1") (pintype "passive"))
      (node (ref "C337") (pin "1") (pinfunction "1_1") (pintype "passive"))
      (node (ref "C338") (pin "1") (pinfunction "1_1") (pintype "passive"))
      (node (ref "C339") (pin "1") (pinfunction "1_1") (pintype "passive"))
      (node (ref "C340") (pin "1") (pinfunction "1_1") (pintype "passive"))
      (node (ref "C341") (pin "1") (pinfunction "1_1") (pintype "passive"))
      (node (ref "C342") (pin "1") (pinfunction "1_1") (pintype "passive"))
      (node (ref "C343") (pin "1") (pinfunction "1_1") (pintype "passive"))
      (node (ref "C344") (pin "1") (pinfunction "1_1") (pintype "passive"))
      (node (ref "C345") (pin "1") (pinfunction "1_1") (pintype "passive"))
      (node (ref "C346") (pin "1") (pinfunction "1_1") (pintype "passive"))
      (node (ref "U2") (pin "A1") (pinfunction "VSS_A1") (pintype "passive"))
      (node (ref "U2") (pin "A10") (pinfunction "VSS_A10") (pintype "passive"))
      (node (ref "U2") (pin "A12") (pinfunction "VSS_A12") (pintype "passive"))
      (node (ref "U2") (pin "A19") (pinfunction "VSS_A19") (pintype "passive"))
      (node (ref "U2") (pin "A2") (pinfunction "VSS_A2") (pintype "passive"))
      (node (ref "U2") (pin "A29") (pinfunction "VSS_A29") (pintype "passive"))
      (node (ref "U2") (pin "A35") (pinfunction "VSS_A35") (pintype "passive"))
      (node (ref "U2") (pin "A36") (pinfunction "VSS_A36") (pintype "passive"))
      (node (ref "U2") (pin "AA11") (pinfunction "VSS_AA11") (pintype "passive"))
      (node (ref "U2") (pin "AA13") (pinfunction "VSS_AA13") (pintype "passive"))
      (node (ref "U2") (pin "AA15") (pinfunction "VSS_AA15") (pintype "passive"))
      (node (ref "U2") (pin "AA17") (pinfunction "VSS_AA17") (pintype "passive"))
      (node (ref "U2") (pin "AA20") (pinfunction "VSS_AA20") (pintype "passive"))
      (node (ref "U2") (pin "AA22") (pinfunction "VSS_AA22") (pintype "passive"))
      (node (ref "U2") (pin "AA24") (pinfunction "VSS_AA24") (pintype "passive"))
      (node (ref "U2") (pin "AA26") (pinfunction "VSS_AA26") (pintype "passive"))
      (node (ref "U2") (pin "AA28") (pinfunction "VSS_AA28") (pintype "passive"))
      (node (ref "U2") (pin "AA3") (pinfunction "VSS_AA3") (pintype "passive"))
      (node (ref "U2") (pin "AA30") (pinfunction "VSS_AA30") (pintype "passive"))
      (node (ref "U2") (pin "AA32") (pinfunction "VSS_AA32") (pintype "passive"))
      (node (ref "U2") (pin "AA5") (pinfunction "VSS_AA5") (pintype "passive"))
      (node (ref "U2") (pin "AA7") (pinfunction "VSS_AA7") (pintype "passive"))
      (node (ref "U2") (pin "AA9") (pinfunction "VSS_AA9") (pintype "passive"))
      (node (ref "U2") (pin "AB10") (pinfunction "VSS_AB10") (pintype "passive"))
      (node (ref "U2") (pin "AB12") (pinfunction "VSS_AB12") (pintype "passive"))
      (node (ref "U2") (pin "AB14") (pinfunction "VSS_AB14") (pintype "passive"))
      (node (ref "U2") (pin "AB16") (pinfunction "VSS_AB16") (pintype "passive"))
      (node (ref "U2") (pin "AB18") (pinfunction "VSS_AB18") (pintype "passive"))
      (node (ref "U2") (pin "AB19") (pinfunction "VSS_AB19") (pintype "passive"))
      (node (ref "U2") (pin "AB21") (pinfunction "VSS_AB21") (pintype "passive"))
      (node (ref "U2") (pin "AB23") (pinfunction "VSS_AB23") (pintype "passive"))
      (node (ref "U2") (pin "AB25") (pinfunction "VSS_AB25") (pintype "passive"))
      (node (ref "U2") (pin "AB27") (pinfunction "VSS_AB27") (pintype "passive"))
      (node (ref "U2") (pin "AB29") (pinfunction "VSS_AB29") (pintype "passive"))
      (node (ref "U2") (pin "AB31") (pinfunction "VSS_AB31") (pintype "passive"))
      (node (ref "U2") (pin "AB6") (pinfunction "VSS_AB6") (pintype "passive"))
      (node (ref "U2") (pin "AB8") (pinfunction "VSS_AB8") (pintype "passive"))
      (node (ref "U2") (pin "AC11") (pinfunction "VSS_AC11") (pintype "passive"))
      (node (ref "U2") (pin "AC13") (pinfunction "VSS_AC13") (pintype "passive"))
      (node (ref "U2") (pin "AC15") (pinfunction "VSS_AC15") (pintype "passive"))
      (node (ref "U2") (pin "AC17") (pinfunction "VSS_AC17") (pintype "passive"))
      (node (ref "U2") (pin "AC20") (pinfunction "VSS_AC20") (pintype "passive"))
      (node (ref "U2") (pin "AC22") (pinfunction "VSS_AC22") (pintype "passive"))
      (node (ref "U2") (pin "AC24") (pinfunction "VSS_AC24") (pintype "passive"))
      (node (ref "U2") (pin "AC26") (pinfunction "VSS_AC26") (pintype "passive"))
      (node (ref "U2") (pin "AC28") (pinfunction "VSS_AC28") (pintype "passive"))
      (node (ref "U2") (pin "AC30") (pinfunction "VSS_AC30") (pintype "passive"))
      (node (ref "U2") (pin "AC32") (pinfunction "VSS_AC32") (pintype "passive"))
      (node (ref "U2") (pin "AC34") (pinfunction "VSS_AC34") (pintype "passive"))
      (node (ref "U2") (pin "AC5") (pinfunction "VSS_AC5") (pintype "passive"))
      (node (ref "U2") (pin "AC7") (pinfunction "VSS_AC7") (pintype "passive"))
      (node (ref "U2") (pin "AC9") (pinfunction "VSS_AC9") (pintype "passive"))
      (node (ref "U2") (pin "AD10") (pinfunction "VSS_AD10") (pintype "passive"))
      (node (ref "U2") (pin "AD12") (pinfunction "VSS_AD12") (pintype "passive"))
      (node (ref "U2") (pin "AD14") (pinfunction "VSS_AD14") (pintype "passive"))
      (node (ref "U2") (pin "AD16") (pinfunction "VSS_AD16") (pintype "passive"))
      (node (ref "U2") (pin "AD18") (pinfunction "VSS_AD18") (pintype "passive"))
      (node (ref "U2") (pin "AD19") (pinfunction "VSS_AD19") (pintype "passive"))
      (node (ref "U2") (pin "AD21") (pinfunction "VSS_AD21") (pintype "passive"))
      (node (ref "U2") (pin "AD23") (pinfunction "VSS_AD23") (pintype "passive"))
      (node (ref "U2") (pin "AD25") (pinfunction "VSS_AD25") (pintype "passive"))
      (node (ref "U2") (pin "AD27") (pinfunction "VSS_AD27") (pintype "passive"))
      (node (ref "U2") (pin "AD29") (pinfunction "VSS_AD29") (pintype "passive"))
      (node (ref "U2") (pin "AD31") (pinfunction "VSS_AD31") (pintype "passive"))
      (node (ref "U2") (pin "AD4") (pinfunction "VSS_AD4") (pintype "passive"))
      (node (ref "U2") (pin "AD6") (pinfunction "VSS_AD6") (pintype "passive"))
      (node (ref "U2") (pin "AD8") (pinfunction "VSS_AD8") (pintype "passive"))
      (node (ref "U2") (pin "AE1") (pinfunction "VSS_AE1") (pintype "passive"))
      (node (ref "U2") (pin "AE11") (pinfunction "VSS_AE11") (pintype "passive"))
      (node (ref "U2") (pin "AE13") (pinfunction "VSS_AE13") (pintype "passive"))
      (node (ref "U2") (pin "AE15") (pinfunction "VSS_AE15") (pintype "passive"))
      (node (ref "U2") (pin "AE17") (pinfunction "VSS_AE17") (pintype "passive"))
      (node (ref "U2") (pin "AE20") (pinfunction "VSS_AE20") (pintype "passive"))
      (node (ref "U2") (pin "AE22") (pinfunction "VSS_AE22") (pintype "passive"))
      (node (ref "U2") (pin "AE24") (pinfunction "VSS_AE24") (pintype "passive"))
      (node (ref "U2") (pin "AE26") (pinfunction "VSS_AE26") (pintype "passive"))
      (node (ref "U2") (pin "AE28") (pinfunction "VSS_AE28") (pintype "passive"))
      (node (ref "U2") (pin "AE30") (pinfunction "VSS_AE30") (pintype "passive"))
      (node (ref "U2") (pin "AE32") (pinfunction "VSS_AE32") (pintype "passive"))
      (node (ref "U2") (pin "AE5") (pinfunction "VSS_AE5") (pintype "passive"))
      (node (ref "U2") (pin "AE7") (pinfunction "VSS_AE7") (pintype "passive"))
      (node (ref "U2") (pin "AE9") (pinfunction "VSS_AE9") (pintype "passive"))
      (node (ref "U2") (pin "AF10") (pinfunction "VSS_AF10") (pintype "passive"))
      (node (ref "U2") (pin "AF12") (pinfunction "VSS_AF12") (pintype "passive"))
      (node (ref "U2") (pin "AF14") (pinfunction "VSS_AF14") (pintype "passive"))
      (node (ref "U2") (pin "AF16") (pinfunction "VSS_AF16") (pintype "passive"))
      (node (ref "U2") (pin "AF18") (pinfunction "VSS_AF18") (pintype "passive"))
      (node (ref "U2") (pin "AF19") (pinfunction "VSS_AF19") (pintype "passive"))
      (node (ref "U2") (pin "AF21") (pinfunction "VSS_AF21") (pintype "passive"))
      (node (ref "U2") (pin "AF23") (pinfunction "VSS_AF23") (pintype "passive"))
      (node (ref "U2") (pin "AF25") (pinfunction "VSS_AF25") (pintype "passive"))
      (node (ref "U2") (pin "AF27") (pinfunction "VSS_AF27") (pintype "passive"))
      (node (ref "U2") (pin "AF29") (pinfunction "VSS_AF29") (pintype "passive"))
      (node (ref "U2") (pin "AF31") (pinfunction "VSS_AF31") (pintype "passive"))
      (node (ref "U2") (pin "AF35") (pinfunction "VSS_AF35") (pintype "passive"))
      (node (ref "U2") (pin "AF8") (pinfunction "VSS_AF8") (pintype "passive"))
      (node (ref "U2") (pin "AG1") (pinfunction "VSS_AG1") (pintype "passive"))
      (node (ref "U2") (pin "AG11") (pinfunction "VSS_AG11") (pintype "passive"))
      (node (ref "U2") (pin "AG13") (pinfunction "VSS_AG13") (pintype "passive"))
      (node (ref "U2") (pin "AG15") (pinfunction "VSS_AG15") (pintype "passive"))
      (node (ref "U2") (pin "AG17") (pinfunction "VSS_AG17") (pintype "passive"))
      (node (ref "U2") (pin "AG20") (pinfunction "VSS_AG20") (pintype "passive"))
      (node (ref "U2") (pin "AG22") (pinfunction "VSS_AG22") (pintype "passive"))
      (node (ref "U2") (pin "AG24") (pinfunction "VSS_AG24") (pintype "passive"))
      (node (ref "U2") (pin "AG26") (pinfunction "VSS_AG26") (pintype "passive"))
      (node (ref "U2") (pin "AG28") (pinfunction "VSS_AG28") (pintype "passive"))
      (node (ref "U2") (pin "AG30") (pinfunction "VSS_AG30") (pintype "passive"))
      (node (ref "U2") (pin "AG32") (pinfunction "VSS_AG32") (pintype "passive"))
      (node (ref "U2") (pin "AG5") (pinfunction "VSS_AG5") (pintype "passive"))
      (node (ref "U2") (pin "AG7") (pinfunction "VSS_AG7") (pintype "passive"))
      (node (ref "U2") (pin "AG9") (pinfunction "VSS_AG9") (pintype "passive"))
      (node (ref "U2") (pin "AH10") (pinfunction "VSS_AH10") (pintype "passive"))
      (node (ref "U2") (pin "AH12") (pinfunction "VSS_AH12") (pintype "passive"))
      (node (ref "U2") (pin "AH14") (pinfunction "VSS_AH14") (pintype "passive"))
      (node (ref "U2") (pin "AH16") (pinfunction "VSS_AH16") (pintype "passive"))
      (node (ref "U2") (pin "AH18") (pinfunction "VSS_AH18") (pintype "passive"))
      (node (ref "U2") (pin "AH19") (pinfunction "VSS_AH19") (pintype "passive"))
      (node (ref "U2") (pin "AH2") (pinfunction "VSS_AH2") (pintype "passive"))
      (node (ref "U2") (pin "AH21") (pinfunction "VSS_AH21") (pintype "passive"))
      (node (ref "U2") (pin "AH23") (pinfunction "VSS_AH23") (pintype "passive"))
      (node (ref "U2") (pin "AH25") (pinfunction "VSS_AH25") (pintype "passive"))
      (node (ref "U2") (pin "AH27") (pinfunction "VSS_AH27") (pintype "passive"))
      (node (ref "U2") (pin "AH29") (pinfunction "VSS_AH29") (pintype "passive"))
      (node (ref "U2") (pin "AH31") (pinfunction "VSS_AH31") (pintype "passive"))
      (node (ref "U2") (pin "AH6") (pinfunction "VSS_AH6") (pintype "passive"))
      (node (ref "U2") (pin "AH8") (pinfunction "VSS_AH8") (pintype "passive"))
      (node (ref "U2") (pin "AJ11") (pinfunction "VSS_AJ11") (pintype "passive"))
      (node (ref "U2") (pin "AJ13") (pinfunction "VSS_AJ13") (pintype "passive"))
      (node (ref "U2") (pin "AJ15") (pinfunction "VSS_AJ15") (pintype "passive"))
      (node (ref "U2") (pin "AJ17") (pinfunction "VSS_AJ17") (pintype "passive"))
      (node (ref "U2") (pin "AJ20") (pinfunction "VSS_AJ20") (pintype "passive"))
      (node (ref "U2") (pin "AJ22") (pinfunction "VSS_AJ22") (pintype "passive"))
      (node (ref "U2") (pin "AJ24") (pinfunction "VSS_AJ24") (pintype "passive"))
      (node (ref "U2") (pin "AJ26") (pinfunction "VSS_AJ26") (pintype "passive"))
      (node (ref "U2") (pin "AJ28") (pinfunction "VSS_AJ28") (pintype "passive"))
      (node (ref "U2") (pin "AJ30") (pinfunction "VSS_AJ30") (pintype "passive"))
      (node (ref "U2") (pin "AJ32") (pinfunction "VSS_AJ32") (pintype "passive"))
      (node (ref "U2") (pin "AJ36") (pinfunction "VSS_AJ36") (pintype "passive"))
      (node (ref "U2") (pin "AJ5") (pinfunction "VSS_AJ5") (pintype "passive"))
      (node (ref "U2") (pin "AJ7") (pinfunction "VSS_AJ7") (pintype "passive"))
      (node (ref "U2") (pin "AJ9") (pinfunction "VSS_AJ9") (pintype "passive"))
      (node (ref "U2") (pin "AK10") (pinfunction "VSS_AK10") (pintype "passive"))
      (node (ref "U2") (pin "AK12") (pinfunction "VSS_AK12") (pintype "passive"))
      (node (ref "U2") (pin "AK14") (pinfunction "VSS_AK14") (pintype "passive"))
      (node (ref "U2") (pin "AK16") (pinfunction "VSS_AK16") (pintype "passive"))
      (node (ref "U2") (pin "AK18") (pinfunction "VSS_AK18") (pintype "passive"))
      (node (ref "U2") (pin "AK19") (pinfunction "VSS_AK19") (pintype "passive"))
      (node (ref "U2") (pin "AK21") (pinfunction "VSS_AK21") (pintype "passive"))
      (node (ref "U2") (pin "AK23") (pinfunction "VSS_AK23") (pintype "passive"))
      (node (ref "U2") (pin "AK25") (pinfunction "VSS_AK25") (pintype "passive"))
      (node (ref "U2") (pin "AK27") (pinfunction "VSS_AK27") (pintype "passive"))
      (node (ref "U2") (pin "AK29") (pinfunction "VSS_AK29") (pintype "passive"))
      (node (ref "U2") (pin "AK31") (pinfunction "VSS_AK31") (pintype "passive"))
      (node (ref "U2") (pin "AK33") (pinfunction "VSS_AK33") (pintype "passive"))
      (node (ref "U2") (pin "AK6") (pinfunction "VSS_AK6") (pintype "passive"))
      (node (ref "U2") (pin "AK8") (pinfunction "VSS_AK8") (pintype "passive"))
      (node (ref "U2") (pin "AL11") (pinfunction "VSS_AL11") (pintype "passive"))
      (node (ref "U2") (pin "AL13") (pinfunction "VSS_AL13") (pintype "passive"))
      (node (ref "U2") (pin "AL15") (pinfunction "VSS_AL15") (pintype "passive"))
      (node (ref "U2") (pin "AL17") (pinfunction "VSS_AL17") (pintype "passive"))
      (node (ref "U2") (pin "AL20") (pinfunction "VSS_AL20") (pintype "passive"))
      (node (ref "U2") (pin "AL22") (pinfunction "VSS_AL22") (pintype "passive"))
      (node (ref "U2") (pin "AL24") (pinfunction "VSS_AL24") (pintype "passive"))
      (node (ref "U2") (pin "AL28") (pinfunction "VSS_AL28") (pintype "passive"))
      (node (ref "U2") (pin "AL3") (pinfunction "VSS_AL3") (pintype "passive"))
      (node (ref "U2") (pin "AL30") (pinfunction "VSS_AL30") (pintype "passive"))
      (node (ref "U2") (pin "AL5") (pinfunction "VSS_AL5") (pintype "passive"))
      (node (ref "U2") (pin "AL7") (pinfunction "VSS_AL7") (pintype "passive"))
      (node (ref "U2") (pin "AL9") (pinfunction "VSS_AL9") (pintype "passive"))
      (node (ref "U2") (pin "AM10") (pinfunction "VSS_AM10") (pintype "passive"))
      (node (ref "U2") (pin "AM12") (pinfunction "VSS_AM12") (pintype "passive"))
      (node (ref "U2") (pin "AM14") (pinfunction "VSS_AM14") (pintype "passive"))
      (node (ref "U2") (pin "AM16") (pinfunction "VSS_AM16") (pintype "passive"))
      (node (ref "U2") (pin "AM18") (pinfunction "VSS_AM18") (pintype "passive"))
      (node (ref "U2") (pin "AM20") (pinfunction "VSS_AM20") (pintype "passive"))
      (node (ref "U2") (pin "AM21") (pinfunction "VSS_AM21") (pintype "passive"))
      (node (ref "U2") (pin "AM23") (pinfunction "VSS_AM23") (pintype "passive"))
      (node (ref "U2") (pin "AM25") (pinfunction "VSS_AM25") (pintype "passive"))
      (node (ref "U2") (pin "AM27") (pinfunction "VSS_AM27") (pintype "passive"))
      (node (ref "U2") (pin "AM29") (pinfunction "VSS_AM29") (pintype "passive"))
      (node (ref "U2") (pin "AM31") (pinfunction "VSS_AM31") (pintype "passive"))
      (node (ref "U2") (pin "AM35") (pinfunction "VSS_AM35") (pintype "passive"))
      (node (ref "U2") (pin "AM8") (pinfunction "VSS_AM8") (pintype "passive"))
      (node (ref "U2") (pin "AN17") (pinfunction "VSS_AN17") (pintype "passive"))
      (node (ref "U2") (pin "AN24") (pinfunction "VSS_AN24") (pintype "passive"))
      (node (ref "U2") (pin "AN34") (pinfunction "VSS_AN34") (pintype "passive"))
      (node (ref "U2") (pin "AN7") (pinfunction "VSS_AN7") (pintype "passive"))
      (node (ref "U2") (pin "AP14") (pinfunction "VSS_AP14") (pintype "passive"))
      (node (ref "U2") (pin "AP18") (pinfunction "VSS_AP18") (pintype "passive"))
      (node (ref "U2") (pin "AP21") (pinfunction "VSS_AP21") (pintype "passive"))
      (node (ref "U2") (pin "AP31") (pinfunction "VSS_AP31") (pintype "passive"))
      (node (ref "U2") (pin "AP4") (pinfunction "VSS_AP4") (pintype "passive"))
      (node (ref "U2") (pin "AR1") (pinfunction "VSS_AR1") (pintype "passive"))
      (node (ref "U2") (pin "AR11") (pinfunction "VSS_AR11") (pintype "passive"))
      (node (ref "U2") (pin "AR28") (pinfunction "VSS_AR28") (pintype "passive"))
      (node (ref "U2") (pin "AR36") (pinfunction "VSS_AR36") (pintype "passive"))
      (node (ref "U2") (pin "AR5") (pinfunction "VSS_AR5") (pintype "passive"))
      (node (ref "U2") (pin "AT1") (pinfunction "VSS_AT1") (pintype "passive"))
      (node (ref "U2") (pin "AT18") (pinfunction "VSS_AT18") (pintype "passive"))
      (node (ref "U2") (pin "AT2") (pinfunction "VSS_AT2") (pintype "passive"))
      (node (ref "U2") (pin "AT25") (pinfunction "VSS_AT25") (pintype "passive"))
      (node (ref "U2") (pin "AT27") (pinfunction "VSS_AT27") (pintype "passive"))
      (node (ref "U2") (pin "AT35") (pinfunction "VSS_AT35") (pintype "passive"))
      (node (ref "U2") (pin "AT36") (pinfunction "VSS_AT36") (pintype "passive"))
      (node (ref "U2") (pin "AT8") (pinfunction "VSS_AT8") (pintype "passive"))
      (node (ref "U2") (pin "B1") (pinfunction "VSS_B1") (pintype "passive"))
      (node (ref "U2") (pin "B26") (pinfunction "VSS_B26") (pintype "passive"))
      (node (ref "U2") (pin "B32") (pinfunction "VSS_B32") (pintype "passive"))
      (node (ref "U2") (pin "B36") (pinfunction "VSS_B36") (pintype "passive"))
      (node (ref "U2") (pin "B9") (pinfunction "VSS_B9") (pintype "passive"))
      (node (ref "U2") (pin "C16") (pinfunction "VSS_C16") (pintype "passive"))
      (node (ref "U2") (pin "C19") (pinfunction "VSS_C19") (pintype "passive"))
      (node (ref "U2") (pin "C23") (pinfunction "VSS_C23") (pintype "passive"))
      (node (ref "U2") (pin "C33") (pinfunction "VSS_C33") (pintype "passive"))
      (node (ref "U2") (pin "C6") (pinfunction "VSS_C6") (pintype "passive"))
      (node (ref "U2") (pin "D13") (pinfunction "VSS_D13") (pintype "passive"))
      (node (ref "U2") (pin "D20") (pinfunction "VSS_D20") (pintype "passive"))
      (node (ref "U2") (pin "D3") (pinfunction "VSS_D3") (pintype "passive"))
      (node (ref "U2") (pin "D30") (pinfunction "VSS_D30") (pintype "passive"))
      (node (ref "U2") (pin "E10") (pinfunction "VSS_E10") (pintype "passive"))
      (node (ref "U2") (pin "E12") (pinfunction "VSS_E12") (pintype "passive"))
      (node (ref "U2") (pin "E14") (pinfunction "VSS_E14") (pintype "passive"))
      (node (ref "U2") (pin "E16") (pinfunction "VSS_E16") (pintype "passive"))
      (node (ref "U2") (pin "E17") (pinfunction "VSS_E17") (pintype "passive"))
      (node (ref "U2") (pin "E19") (pinfunction "VSS_E19") (pintype "passive"))
      (node (ref "U2") (pin "E2") (pinfunction "VSS_E2") (pintype "passive"))
      (node (ref "U2") (pin "E21") (pinfunction "VSS_E21") (pintype "passive"))
      (node (ref "U2") (pin "E23") (pinfunction "VSS_E23") (pintype "passive"))
      (node (ref "U2") (pin "E25") (pinfunction "VSS_E25") (pintype "passive"))
      (node (ref "U2") (pin "E27") (pinfunction "VSS_E27") (pintype "passive"))
      (node (ref "U2") (pin "E29") (pinfunction "VSS_E29") (pintype "passive"))
      (node (ref "U2") (pin "E6") (pinfunction "VSS_E6") (pintype "passive"))
      (node (ref "U2") (pin "E8") (pinfunction "VSS_E8") (pintype "passive"))
      (node (ref "U2") (pin "F13") (pinfunction "VSS_F13") (pintype "passive"))
      (node (ref "U2") (pin "F15") (pinfunction "VSS_F15") (pintype "passive"))
      (node (ref "U2") (pin "F17") (pinfunction "VSS_F17") (pintype "passive"))
      (node (ref "U2") (pin "F20") (pinfunction "VSS_F20") (pintype "passive"))
      (node (ref "U2") (pin "F22") (pinfunction "VSS_F22") (pintype "passive"))
      (node (ref "U2") (pin "F24") (pinfunction "VSS_F24") (pintype "passive"))
      (node (ref "U2") (pin "F26") (pinfunction "VSS_F26") (pintype "passive"))
      (node (ref "U2") (pin "F28") (pinfunction "VSS_F28") (pintype "passive"))
      (node (ref "U2") (pin "F30") (pinfunction "VSS_F30") (pintype "passive"))
      (node (ref "U2") (pin "F32") (pinfunction "VSS_F32") (pintype "passive"))
      (node (ref "U2") (pin "F34") (pinfunction "VSS_F34") (pintype "passive"))
      (node (ref "U2") (pin "F7") (pinfunction "VSS_F7") (pintype "passive"))
      (node (ref "U2") (pin "F9") (pinfunction "VSS_F9") (pintype "passive"))
      (node (ref "U2") (pin "G10") (pinfunction "VSS_G10") (pintype "passive"))
      (node (ref "U2") (pin "G12") (pinfunction "VSS_G12") (pintype "passive"))
      (node (ref "U2") (pin "G14") (pinfunction "VSS_G14") (pintype "passive"))
      (node (ref "U2") (pin "G16") (pinfunction "VSS_G16") (pintype "passive"))
      (node (ref "U2") (pin "G18") (pinfunction "VSS_G18") (pintype "passive"))
      (node (ref "U2") (pin "G19") (pinfunction "VSS_G19") (pintype "passive"))
      (node (ref "U2") (pin "G21") (pinfunction "VSS_G21") (pintype "passive"))
      (node (ref "U2") (pin "G23") (pinfunction "VSS_G23") (pintype "passive"))
      (node (ref "U2") (pin "G25") (pinfunction "VSS_G25") (pintype "passive"))
      (node (ref "U2") (pin "G27") (pinfunction "VSS_G27") (pintype "passive"))
      (node (ref "U2") (pin "G29") (pinfunction "VSS_G29") (pintype "passive"))
      (node (ref "U2") (pin "G31") (pinfunction "VSS_G31") (pintype "passive"))
      (node (ref "U2") (pin "G4") (pinfunction "VSS_G4") (pintype "passive"))
      (node (ref "U2") (pin "G6") (pinfunction "VSS_G6") (pintype "passive"))
      (node (ref "U2") (pin "G8") (pinfunction "VSS_G8") (pintype "passive"))
      (node (ref "U2") (pin "H1") (pinfunction "VSS_H1") (pintype "passive"))
      (node (ref "U2") (pin "H11") (pinfunction "VSS_H11") (pintype "passive"))
      (node (ref "U2") (pin "H13") (pinfunction "VSS_H13") (pintype "passive"))
      (node (ref "U2") (pin "H15") (pinfunction "VSS_H15") (pintype "passive"))
      (node (ref "U2") (pin "H17") (pinfunction "VSS_H17") (pintype "passive"))
      (node (ref "U2") (pin "H20") (pinfunction "VSS_H20") (pintype "passive"))
      (node (ref "U2") (pin "H22") (pinfunction "VSS_H22") (pintype "passive"))
      (node (ref "U2") (pin "H24") (pinfunction "VSS_H24") (pintype "passive"))
      (node (ref "U2") (pin "H26") (pinfunction "VSS_H26") (pintype "passive"))
      (node (ref "U2") (pin "H28") (pinfunction "VSS_H28") (pintype "passive"))
      (node (ref "U2") (pin "H30") (pinfunction "VSS_H30") (pintype "passive"))
      (node (ref "U2") (pin "H32") (pinfunction "VSS_H32") (pintype "passive"))
      (node (ref "U2") (pin "H5") (pinfunction "VSS_H5") (pintype "passive"))
      (node (ref "U2") (pin "H7") (pinfunction "VSS_H7") (pintype "passive"))
      (node (ref "U2") (pin "H9") (pinfunction "VSS_H9") (pintype "passive"))
      (node (ref "U2") (pin "J10") (pinfunction "VSS_J10") (pintype "passive"))
      (node (ref "U2") (pin "J12") (pinfunction "VSS_J12") (pintype "passive"))
      (node (ref "U2") (pin "J14") (pinfunction "VSS_J14") (pintype "passive"))
      (node (ref "U2") (pin "J16") (pinfunction "VSS_J16") (pintype "passive"))
      (node (ref "U2") (pin "J18") (pinfunction "VSS_J18") (pintype "passive"))
      (node (ref "U2") (pin "J19") (pinfunction "VSS_J19") (pintype "passive"))
      (node (ref "U2") (pin "J21") (pinfunction "VSS_J21") (pintype "passive"))
      (node (ref "U2") (pin "J23") (pinfunction "VSS_J23") (pintype "passive"))
      (node (ref "U2") (pin "J25") (pinfunction "VSS_J25") (pintype "passive"))
      (node (ref "U2") (pin "J27") (pinfunction "VSS_J27") (pintype "passive"))
      (node (ref "U2") (pin "J29") (pinfunction "VSS_J29") (pintype "passive"))
      (node (ref "U2") (pin "J31") (pinfunction "VSS_J31") (pintype "passive"))
      (node (ref "U2") (pin "J35") (pinfunction "VSS_J35") (pintype "passive"))
      (node (ref "U2") (pin "J6") (pinfunction "VSS_J6") (pintype "passive"))
      (node (ref "U2") (pin "J8") (pinfunction "VSS_J8") (pintype "passive"))
      (node (ref "U2") (pin "K11") (pinfunction "VSS_K11") (pintype "passive"))
      (node (ref "U2") (pin "K13") (pinfunction "VSS_K13") (pintype "passive"))
      (node (ref "U2") (pin "K15") (pinfunction "VSS_K15") (pintype "passive"))
      (node (ref "U2") (pin "K17") (pinfunction "VSS_K17") (pintype "passive"))
      (node (ref "U2") (pin "K20") (pinfunction "VSS_K20") (pintype "passive"))
      (node (ref "U2") (pin "K22") (pinfunction "VSS_K22") (pintype "passive"))
      (node (ref "U2") (pin "K24") (pinfunction "VSS_K24") (pintype "passive"))
      (node (ref "U2") (pin "K26") (pinfunction "VSS_K26") (pintype "passive"))
      (node (ref "U2") (pin "K28") (pinfunction "VSS_K28") (pintype "passive"))
      (node (ref "U2") (pin "K30") (pinfunction "VSS_K30") (pintype "passive"))
      (node (ref "U2") (pin "K32") (pinfunction "VSS_K32") (pintype "passive"))
      (node (ref "U2") (pin "K36") (pinfunction "VSS_K36") (pintype "passive"))
      (node (ref "U2") (pin "K5") (pinfunction "VSS_K5") (pintype "passive"))
      (node (ref "U2") (pin "K7") (pinfunction "VSS_K7") (pintype "passive"))
      (node (ref "U2") (pin "K9") (pinfunction "VSS_K9") (pintype "passive"))
      (node (ref "U2") (pin "L10") (pinfunction "VSS_L10") (pintype "passive"))
      (node (ref "U2") (pin "L12") (pinfunction "VSS_L12") (pintype "passive"))
      (node (ref "U2") (pin "L14") (pinfunction "VSS_L14") (pintype "passive"))
      (node (ref "U2") (pin "L16") (pinfunction "VSS_L16") (pintype "passive"))
      (node (ref "U2") (pin "L18") (pinfunction "VSS_L18") (pintype "passive"))
      (node (ref "U2") (pin "L19") (pinfunction "VSS_L19") (pintype "passive"))
      (node (ref "U2") (pin "L2") (pinfunction "VSS_L2") (pintype "passive"))
      (node (ref "U2") (pin "L21") (pinfunction "VSS_L21") (pintype "passive"))
      (node (ref "U2") (pin "L23") (pinfunction "VSS_L23") (pintype "passive"))
      (node (ref "U2") (pin "L25") (pinfunction "VSS_L25") (pintype "passive"))
      (node (ref "U2") (pin "L27") (pinfunction "VSS_L27") (pintype "passive"))
      (node (ref "U2") (pin "L29") (pinfunction "VSS_L29") (pintype "passive"))
      (node (ref "U2") (pin "L6") (pinfunction "VSS_L6") (pintype "passive"))
      (node (ref "U2") (pin "L8") (pinfunction "VSS_L8") (pintype "passive"))
      (node (ref "U2") (pin "M11") (pinfunction "VSS_M11") (pintype "passive"))
      (node (ref "U2") (pin "M13") (pinfunction "VSS_M13") (pintype "passive"))
      (node (ref "U2") (pin "M15") (pinfunction "VSS_M15") (pintype "passive"))
      (node (ref "U2") (pin "M17") (pinfunction "VSS_M17") (pintype "passive"))
      (node (ref "U2") (pin "M20") (pinfunction "VSS_M20") (pintype "passive"))
      (node (ref "U2") (pin "M22") (pinfunction "VSS_M22") (pintype "passive"))
      (node (ref "U2") (pin "M24") (pinfunction "VSS_M24") (pintype "passive"))
      (node (ref "U2") (pin "M26") (pinfunction "VSS_M26") (pintype "passive"))
      (node (ref "U2") (pin "M28") (pinfunction "VSS_M28") (pintype "passive"))
      (node (ref "U2") (pin "M30") (pinfunction "VSS_M30") (pintype "passive"))
      (node (ref "U2") (pin "M32") (pinfunction "VSS_M32") (pintype "passive"))
      (node (ref "U2") (pin "M36") (pinfunction "VSS_M36") (pintype "passive"))
      (node (ref "U2") (pin "M5") (pinfunction "VSS_M5") (pintype "passive"))
      (node (ref "U2") (pin "M7") (pinfunction "VSS_M7") (pintype "passive"))
      (node (ref "U2") (pin "M9") (pinfunction "VSS_M9") (pintype "passive"))
      (node (ref "U2") (pin "N10") (pinfunction "VSS_N10") (pintype "passive"))
      (node (ref "U2") (pin "N12") (pinfunction "VSS_N12") (pintype "passive"))
      (node (ref "U2") (pin "N14") (pinfunction "VSS_N14") (pintype "passive"))
      (node (ref "U2") (pin "N16") (pinfunction "VSS_N16") (pintype "passive"))
      (node (ref "U2") (pin "N18") (pinfunction "VSS_N18") (pintype "passive"))
      (node (ref "U2") (pin "N19") (pinfunction "VSS_N19") (pintype "passive"))
      (node (ref "U2") (pin "N21") (pinfunction "VSS_N21") (pintype "passive"))
      (node (ref "U2") (pin "N23") (pinfunction "VSS_N23") (pintype "passive"))
      (node (ref "U2") (pin "N25") (pinfunction "VSS_N25") (pintype "passive"))
      (node (ref "U2") (pin "N27") (pinfunction "VSS_N27") (pintype "passive"))
      (node (ref "U2") (pin "N29") (pinfunction "VSS_N29") (pintype "passive"))
      (node (ref "U2") (pin "N31") (pinfunction "VSS_N31") (pintype "passive"))
      (node (ref "U2") (pin "N33") (pinfunction "VSS_N33") (pintype "passive"))
      (node (ref "U2") (pin "N6") (pinfunction "VSS_N6") (pintype "passive"))
      (node (ref "U2") (pin "N8") (pinfunction "VSS_N8") (pintype "passive"))
      (node (ref "U2") (pin "P11") (pinfunction "VSS_P11") (pintype "passive"))
      (node (ref "U2") (pin "P13") (pinfunction "VSS_P13") (pintype "passive"))
      (node (ref "U2") (pin "P15") (pinfunction "VSS_P15") (pintype "passive"))
      (node (ref "U2") (pin "P17") (pinfunction "VSS_P17") (pintype "passive"))
      (node (ref "U2") (pin "P20") (pinfunction "VSS_P20") (pintype "passive"))
      (node (ref "U2") (pin "P22") (pinfunction "VSS_P22") (pintype "passive"))
      (node (ref "U2") (pin "P24") (pinfunction "VSS_P24") (pintype "passive"))
      (node (ref "U2") (pin "P26") (pinfunction "VSS_P26") (pintype "passive"))
      (node (ref "U2") (pin "P28") (pinfunction "VSS_P28") (pintype "passive"))
      (node (ref "U2") (pin "P3") (pinfunction "VSS_P3") (pintype "passive"))
      (node (ref "U2") (pin "P30") (pinfunction "VSS_P30") (pintype "passive"))
      (node (ref "U2") (pin "P32") (pinfunction "VSS_P32") (pintype "passive"))
      (node (ref "U2") (pin "P5") (pinfunction "VSS_P5") (pintype "passive"))
      (node (ref "U2") (pin "P7") (pinfunction "VSS_P7") (pintype "passive"))
      (node (ref "U2") (pin "P9") (pinfunction "VSS_P9") (pintype "passive"))
      (node (ref "U2") (pin "R10") (pinfunction "VSS_R10") (pintype "passive"))
      (node (ref "U2") (pin "R12") (pinfunction "VSS_R12") (pintype "passive"))
      (node (ref "U2") (pin "R14") (pinfunction "VSS_R14") (pintype "passive"))
      (node (ref "U2") (pin "R16") (pinfunction "VSS_R16") (pintype "passive"))
      (node (ref "U2") (pin "R18") (pinfunction "VSS_R18") (pintype "passive"))
      (node (ref "U2") (pin "R19") (pinfunction "VSS_R19") (pintype "passive"))
      (node (ref "U2") (pin "R21") (pinfunction "VSS_R21") (pintype "passive"))
      (node (ref "U2") (pin "R23") (pinfunction "VSS_R23") (pintype "passive"))
      (node (ref "U2") (pin "R25") (pinfunction "VSS_R25") (pintype "passive"))
      (node (ref "U2") (pin "R27") (pinfunction "VSS_R27") (pintype "passive"))
      (node (ref "U2") (pin "R29") (pinfunction "VSS_R29") (pintype "passive"))
      (node (ref "U2") (pin "R31") (pinfunction "VSS_R31") (pintype "passive"))
      (node (ref "U2") (pin "R6") (pinfunction "VSS_R6") (pintype "passive"))
      (node (ref "U2") (pin "R8") (pinfunction "VSS_R8") (pintype "passive"))
      (node (ref "U2") (pin "T11") (pinfunction "VSS_T11") (pintype "passive"))
      (node (ref "U2") (pin "T13") (pinfunction "VSS_T13") (pintype "passive"))
      (node (ref "U2") (pin "T15") (pinfunction "VSS_T15") (pintype "passive"))
      (node (ref "U2") (pin "T17") (pinfunction "VSS_T17") (pintype "passive"))
      (node (ref "U2") (pin "T20") (pinfunction "VSS_T20") (pintype "passive"))
      (node (ref "U2") (pin "T22") (pinfunction "VSS_T22") (pintype "passive"))
      (node (ref "U2") (pin "T24") (pinfunction "VSS_T24") (pintype "passive"))
      (node (ref "U2") (pin "T26") (pinfunction "VSS_T26") (pintype "passive"))
      (node (ref "U2") (pin "T28") (pinfunction "VSS_T28") (pintype "passive"))
      (node (ref "U2") (pin "T30") (pinfunction "VSS_T30") (pintype "passive"))
      (node (ref "U2") (pin "T32") (pinfunction "VSS_T32") (pintype "passive"))
      (node (ref "U2") (pin "T34") (pinfunction "VSS_T34") (pintype "passive"))
      (node (ref "U2") (pin "T5") (pinfunction "VSS_T5") (pintype "passive"))
      (node (ref "U2") (pin "T7") (pinfunction "VSS_T7") (pintype "passive"))
      (node (ref "U2") (pin "T9") (pinfunction "VSS_T9") (pintype "passive"))
      (node (ref "U2") (pin "U10") (pinfunction "VSS_U10") (pintype "passive"))
      (node (ref "U2") (pin "U12") (pinfunction "VSS_U12") (pintype "passive"))
      (node (ref "U2") (pin "U14") (pinfunction "VSS_U14") (pintype "passive"))
      (node (ref "U2") (pin "U16") (pinfunction "VSS_U16") (pintype "passive"))
      (node (ref "U2") (pin "U18") (pinfunction "VSS_U18") (pintype "passive"))
      (node (ref "U2") (pin "U19") (pinfunction "VSS_U19") (pintype "passive"))
      (node (ref "U2") (pin "U21") (pinfunction "VSS_U21") (pintype "passive"))
      (node (ref "U2") (pin "U23") (pinfunction "VSS_U23") (pintype "passive"))
      (node (ref "U2") (pin "U25") (pinfunction "VSS_U25") (pintype "passive"))
      (node (ref "U2") (pin "U27") (pinfunction "VSS_U27") (pintype "passive"))
      (node (ref "U2") (pin "U29") (pinfunction "VSS_U29") (pintype "passive"))
      (node (ref "U2") (pin "U31") (pinfunction "VSS_U31") (pintype "passive"))
      (node (ref "U2") (pin "U32") (pinfunction "VSS_U32") (pintype "passive"))
      (node (ref "U2") (pin "U4") (pinfunction "VSS_U4") (pintype "passive"))
      (node (ref "U2") (pin "U6") (pinfunction "VSS_U6") (pintype "passive"))
      (node (ref "U2") (pin "U8") (pinfunction "VSS_U8") (pintype "passive"))
      (node (ref "U2") (pin "V1") (pinfunction "VSS_V1") (pintype "passive"))
      (node (ref "U2") (pin "V11") (pinfunction "VSS_V11") (pintype "passive"))
      (node (ref "U2") (pin "V13") (pinfunction "VSS_V13") (pintype "passive"))
      (node (ref "U2") (pin "V15") (pinfunction "VSS_V15") (pintype "passive"))
      (node (ref "U2") (pin "V17") (pinfunction "VSS_V17") (pintype "passive"))
      (node (ref "U2") (pin "V20") (pinfunction "VSS_V20") (pintype "passive"))
      (node (ref "U2") (pin "V22") (pinfunction "VSS_V22") (pintype "passive"))
      (node (ref "U2") (pin "V24") (pinfunction "VSS_V24") (pintype "passive"))
      (node (ref "U2") (pin "V26") (pinfunction "VSS_V26") (pintype "passive"))
      (node (ref "U2") (pin "V28") (pinfunction "VSS_V28") (pintype "passive"))
      (node (ref "U2") (pin "V3") (pinfunction "VSS_V3") (pintype "passive"))
      (node (ref "U2") (pin "V30") (pinfunction "VSS_V30") (pintype "passive"))
      (node (ref "U2") (pin "V5") (pinfunction "VSS_V5") (pintype "passive"))
      (node (ref "U2") (pin "V7") (pinfunction "VSS_V7") (pintype "passive"))
      (node (ref "U2") (pin "V9") (pinfunction "VSS_V9") (pintype "passive"))
      (node (ref "U2") (pin "W11") (pinfunction "VSS_W11") (pintype "passive"))
      (node (ref "U2") (pin "W13") (pinfunction "VSS_W13") (pintype "passive"))
      (node (ref "U2") (pin "W15") (pinfunction "VSS_W15") (pintype "passive"))
      (node (ref "U2") (pin "W17") (pinfunction "VSS_W17") (pintype "passive"))
      (node (ref "U2") (pin "W20") (pinfunction "VSS_W20") (pintype "passive"))
      (node (ref "U2") (pin "W22") (pinfunction "VSS_W22") (pintype "passive"))
      (node (ref "U2") (pin "W24") (pinfunction "VSS_W24") (pintype "passive"))
      (node (ref "U2") (pin "W26") (pinfunction "VSS_W26") (pintype "passive"))
      (node (ref "U2") (pin "W28") (pinfunction "VSS_W28") (pintype "passive"))
      (node (ref "U2") (pin "W30") (pinfunction "VSS_W30") (pintype "passive"))
      (node (ref "U2") (pin "W32") (pinfunction "VSS_W32") (pintype "passive"))
      (node (ref "U2") (pin "W34") (pinfunction "VSS_W34") (pintype "passive"))
      (node (ref "U2") (pin "W36") (pinfunction "VSS_W36") (pintype "passive"))
      (node (ref "U2") (pin "W7") (pinfunction "VSS_W7") (pintype "passive"))
      (node (ref "U2") (pin "W9") (pinfunction "VSS_W9") (pintype "passive"))
      (node (ref "U2") (pin "Y10") (pinfunction "VSS_Y10") (pintype "passive"))
      (node (ref "U2") (pin "Y12") (pinfunction "VSS_Y12") (pintype "passive"))
      (node (ref "U2") (pin "Y14") (pinfunction "VSS_Y14") (pintype "passive"))
      (node (ref "U2") (pin "Y16") (pinfunction "VSS_Y16") (pintype "passive"))
      (node (ref "U2") (pin "Y18") (pinfunction "VSS_Y18") (pintype "passive"))
      (node (ref "U2") (pin "Y19") (pinfunction "VSS_Y19") (pintype "passive"))
      (node (ref "U2") (pin "Y21") (pinfunction "VSS_Y21") (pintype "passive"))
      (node (ref "U2") (pin "Y23") (pinfunction "VSS_Y23") (pintype "passive"))
      (node (ref "U2") (pin "Y25") (pinfunction "VSS_Y25") (pintype "passive"))
      (node (ref "U2") (pin "Y27") (pinfunction "VSS_Y27") (pintype "passive"))
      (node (ref "U2") (pin "Y29") (pinfunction "VSS_Y29") (pintype "passive"))
      (node (ref "U2") (pin "Y31") (pinfunction "VSS_Y31") (pintype "passive"))
      (node (ref "U2") (pin "Y33") (pinfunction "VSS_Y33") (pintype "passive"))
      (node (ref "U2") (pin "Y5") (pinfunction "VSS_Y5") (pintype "passive"))
      (node (ref "U2") (pin "Y6") (pinfunction "VSS_Y6") (pintype "passive"))
      (node (ref "U2") (pin "Y8") (pinfunction "VSS_Y8") (pintype "passive"))
    )
  )
)
